# Erolf.net
KiCad netlist of a schematic drawn in EAGLE
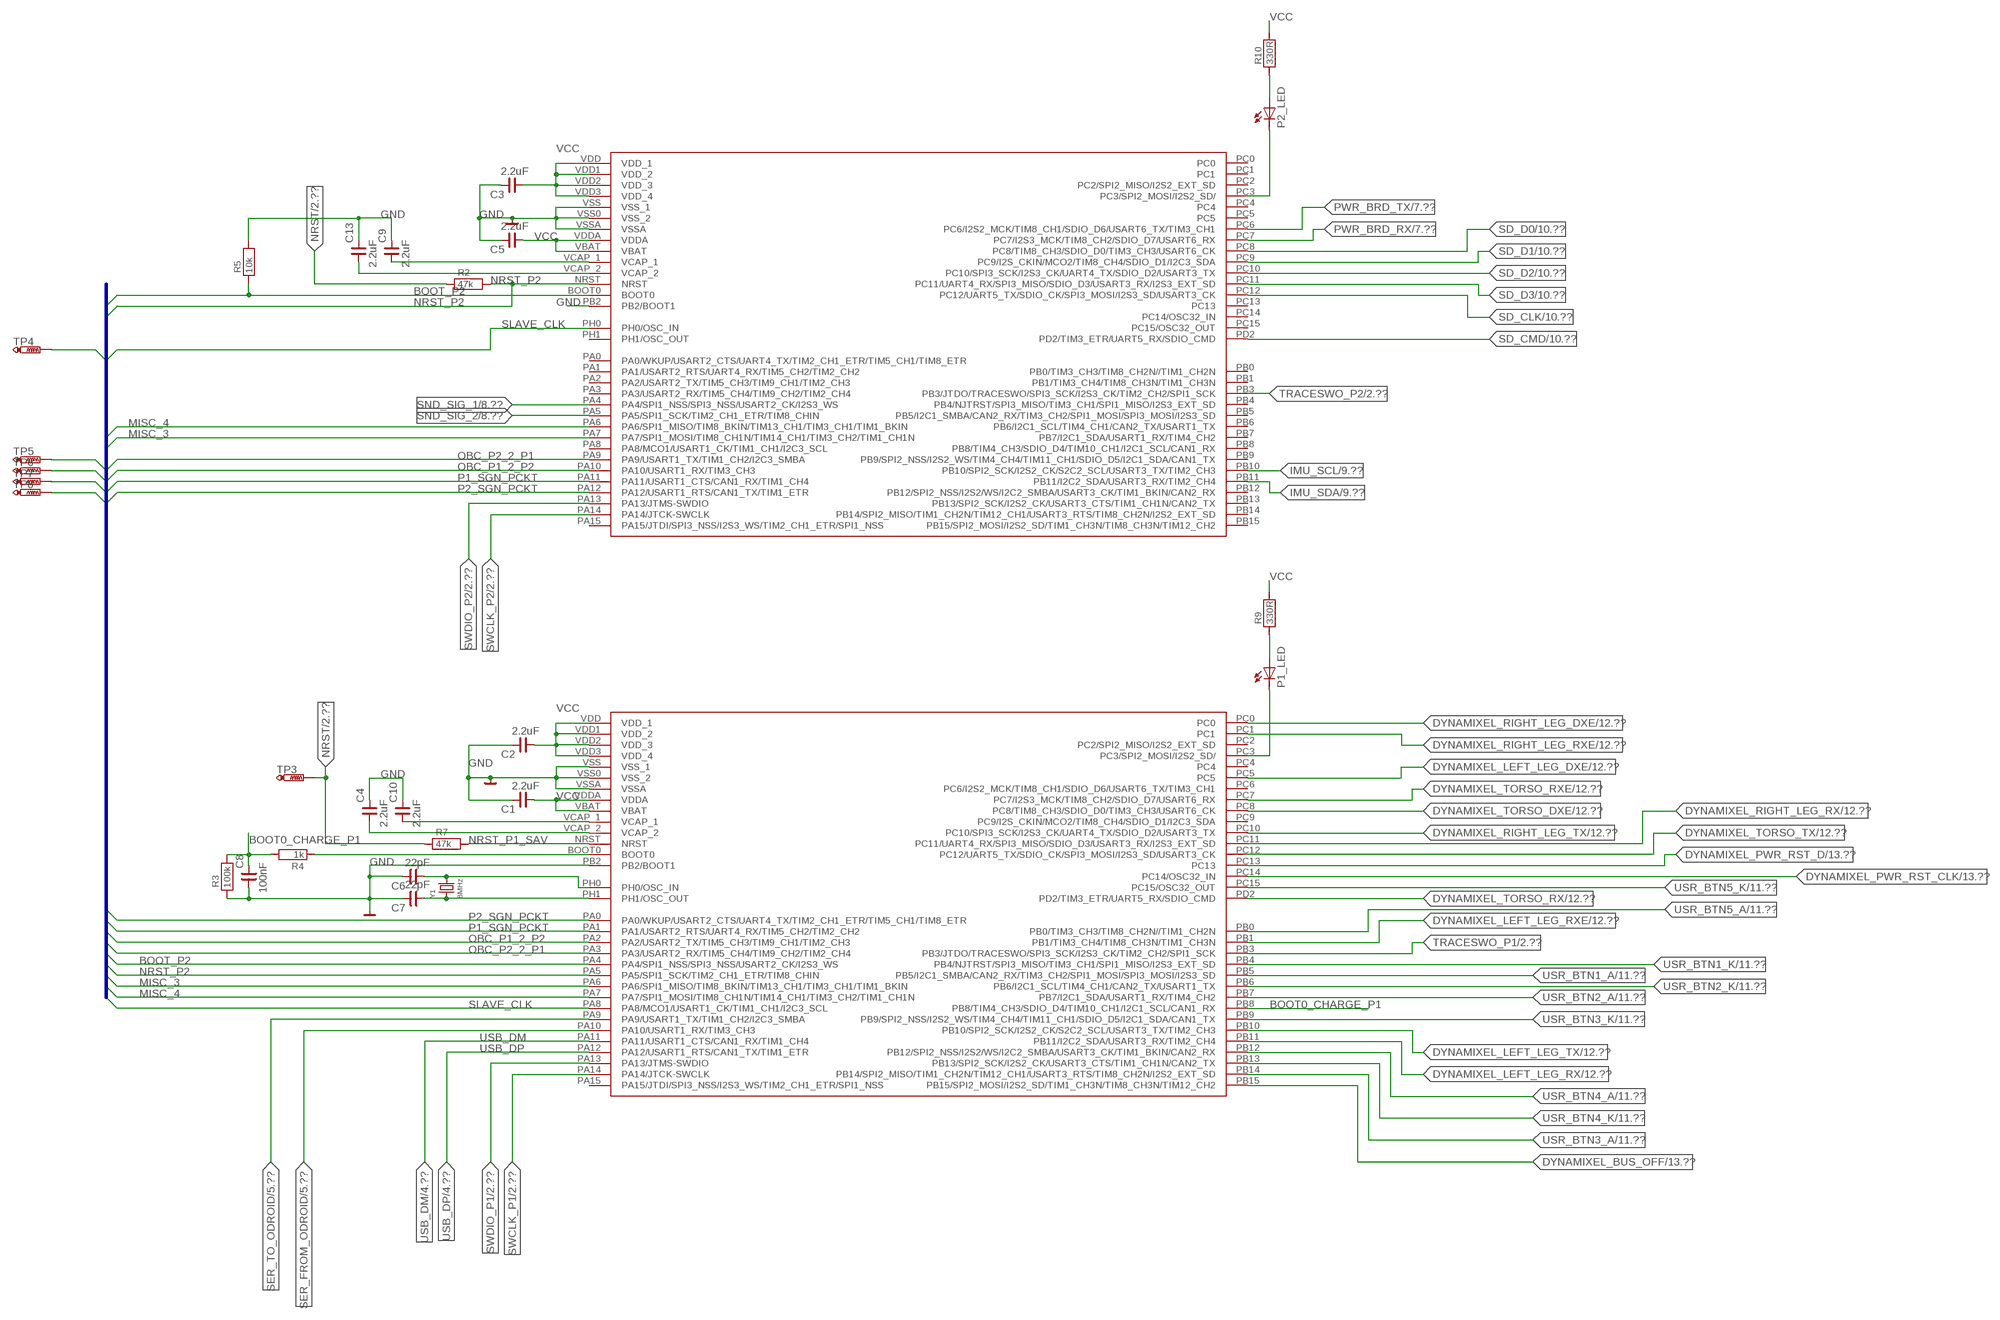
[diagram p0: schematic, sheet 1]
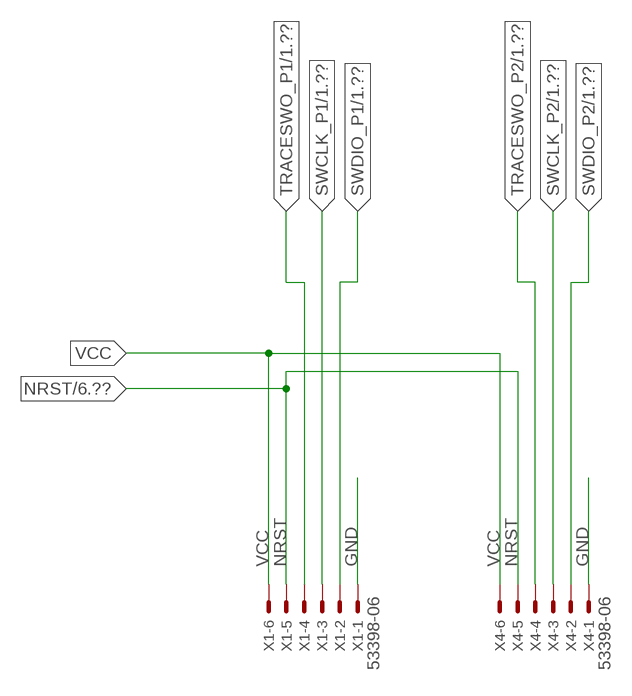
[diagram p1: schematic, sheet 2]
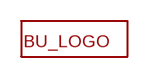
[diagram p2: schematic, sheet 3]
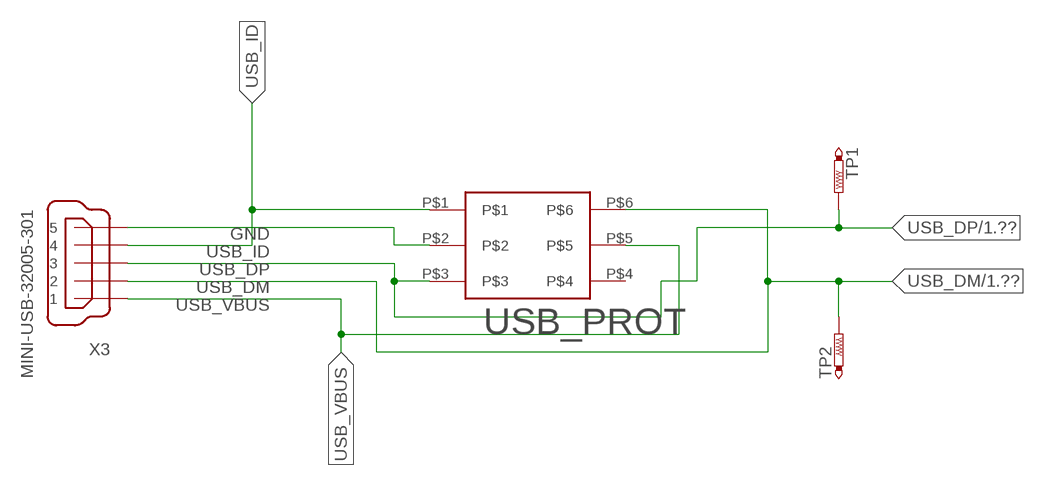
[diagram p3: schematic, sheet 4]
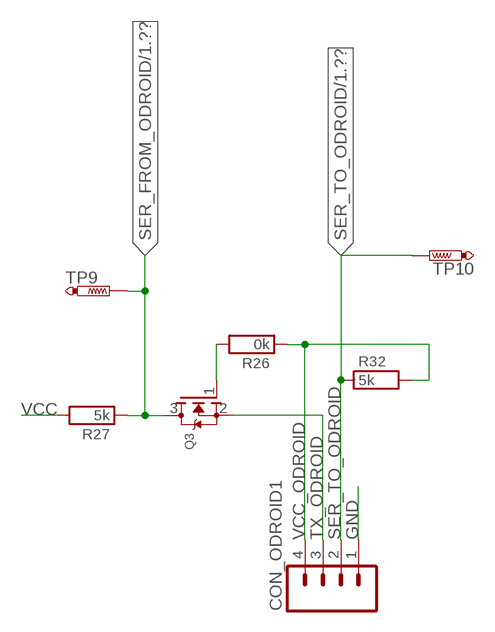
[diagram p4: schematic, sheet 5]
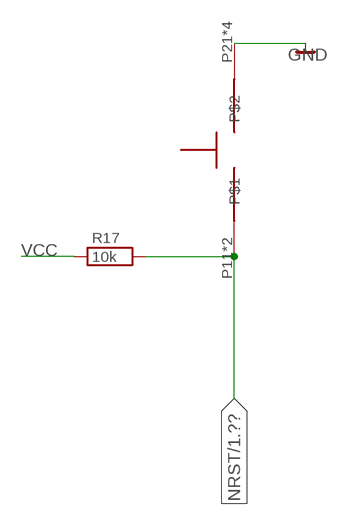
[diagram p5: schematic, sheet 6]
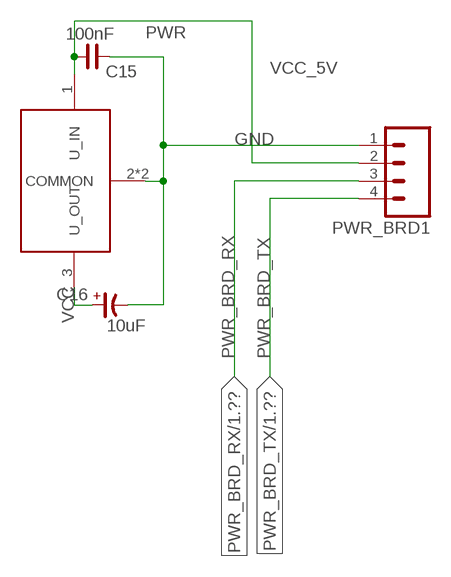
[diagram p6: schematic, sheet 7]
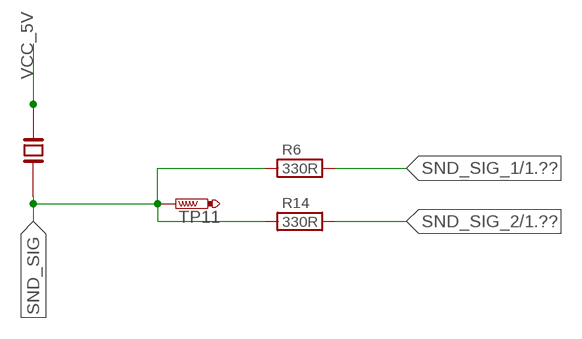
[diagram p7: schematic, sheet 8]
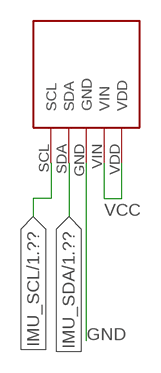
[diagram p8: schematic, sheet 9]
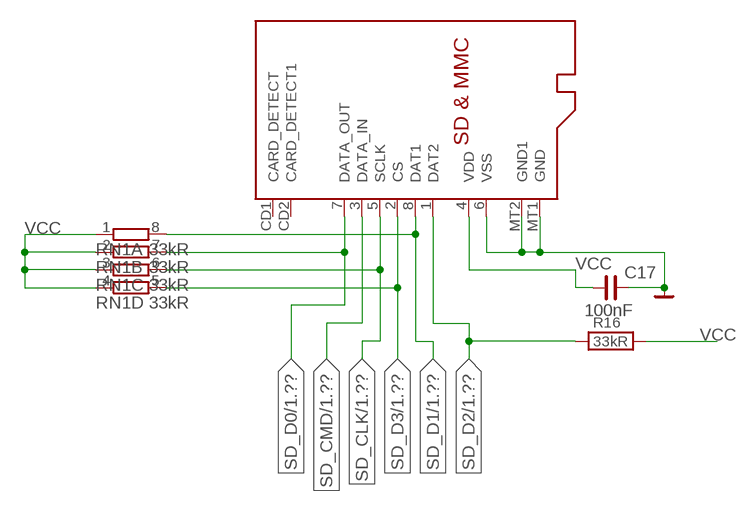
[diagram p9: schematic, sheet 10]
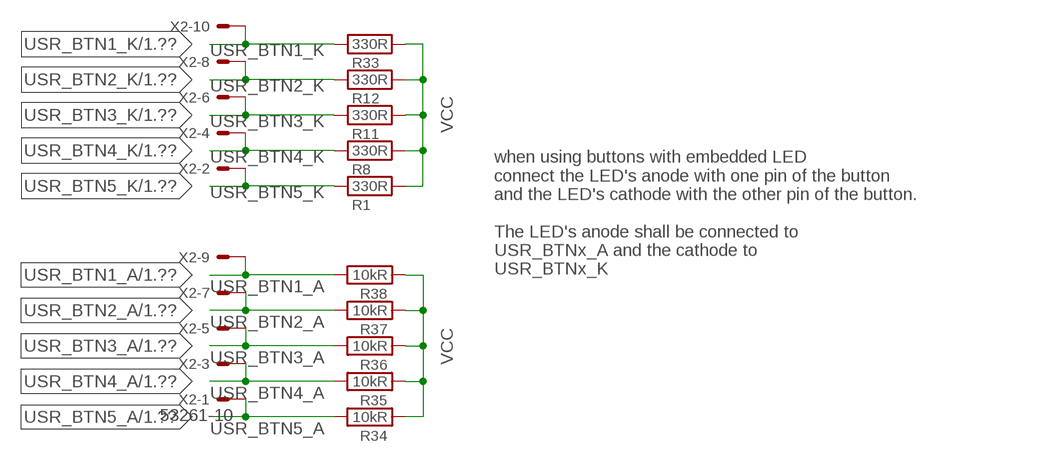
[diagram p10: schematic, sheet 11]
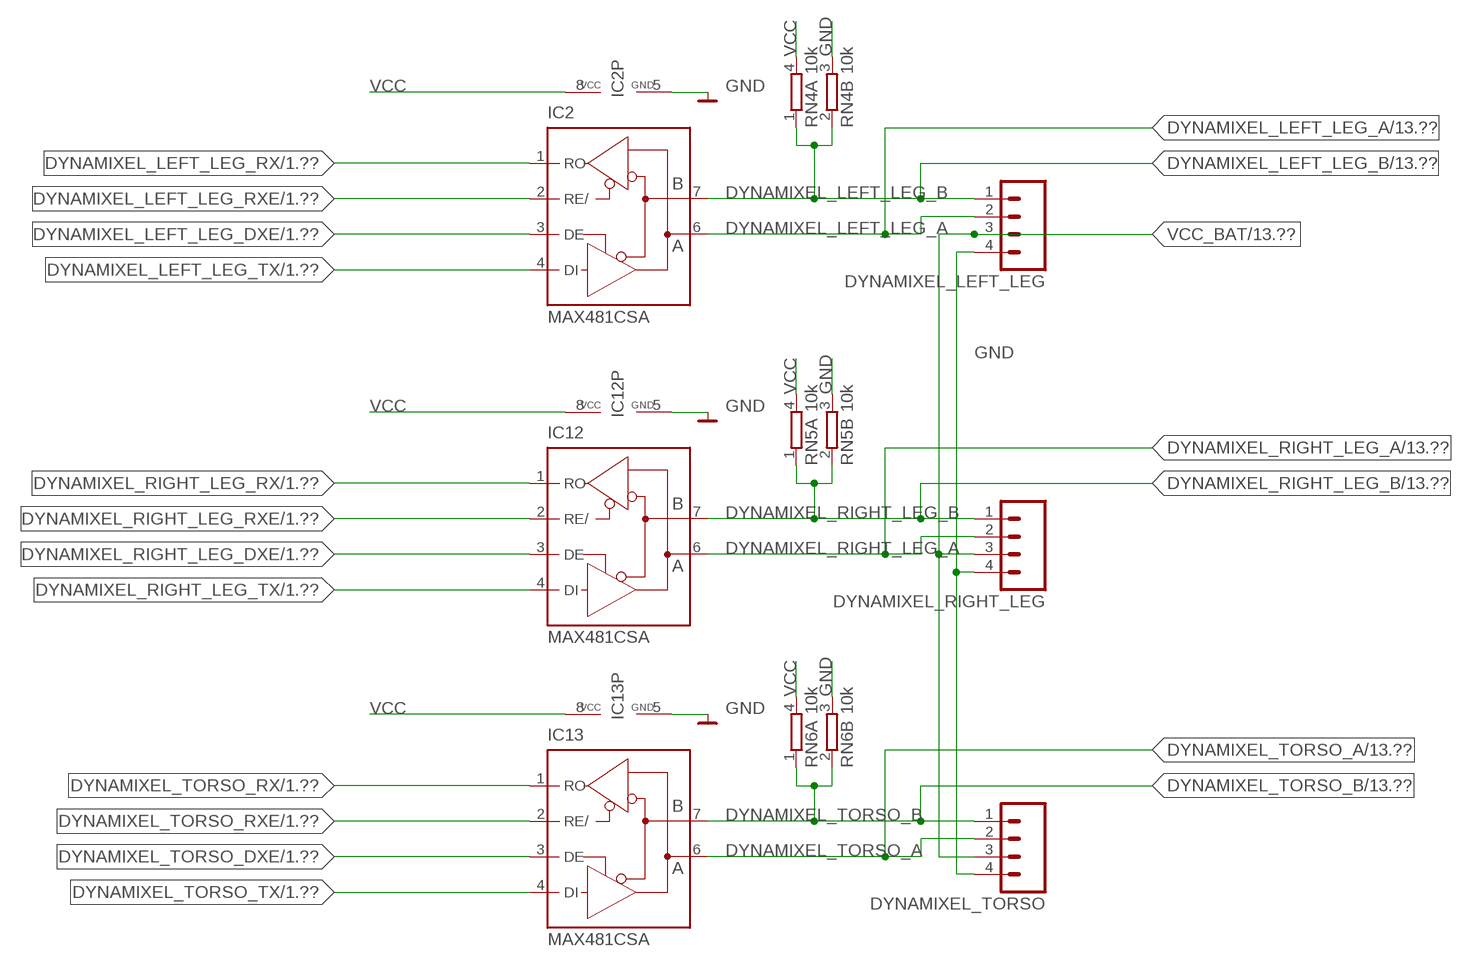
[diagram p11: schematic, sheet 12]
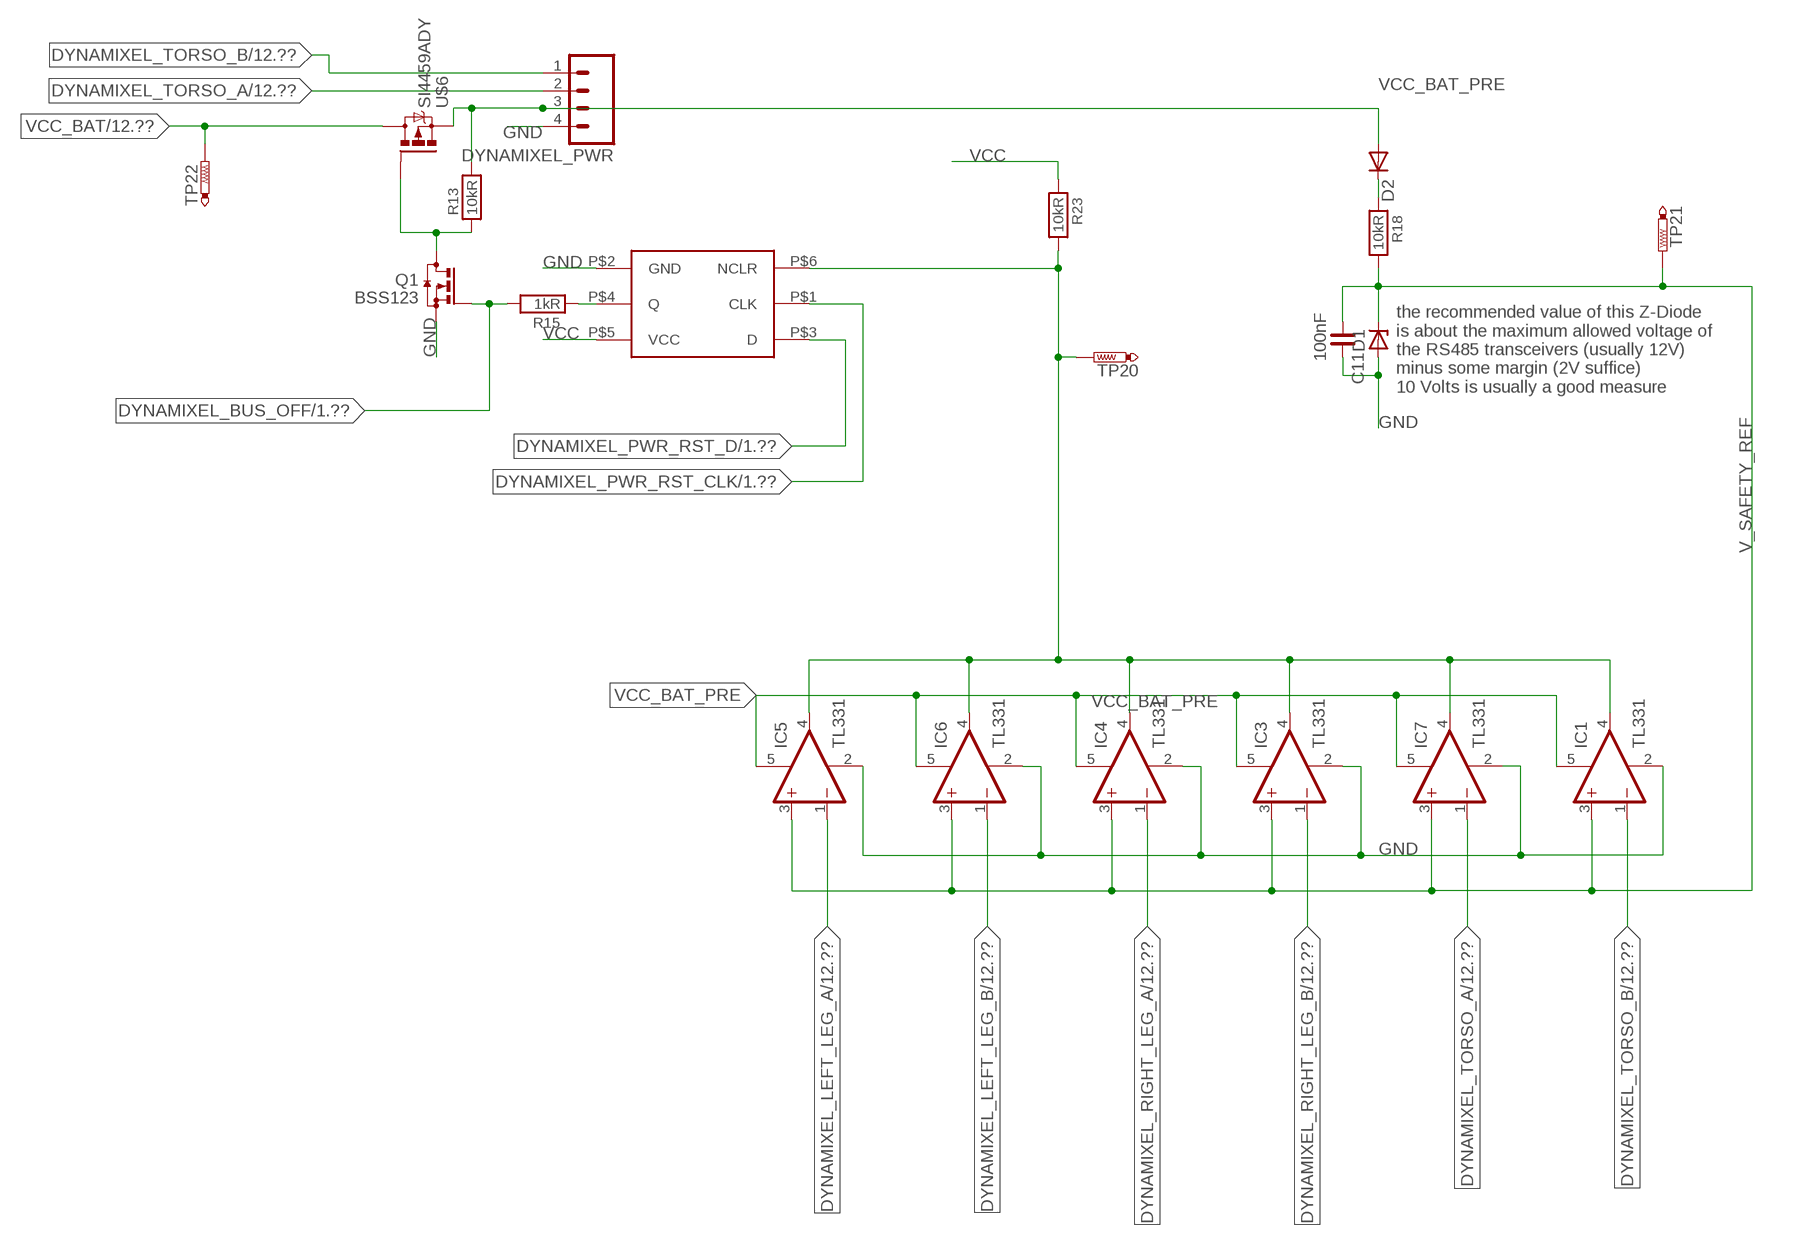
[diagram p12: schematic, sheet 13]

(export (version "E")
  (design (tool "Eeschema 10.0.6"))
  (components
    (comp (ref "TP1")
      (value "PTR1TP06R")
      (footprint "eagle-import:TP06R")
      (libsource (lib "eagle-import") (part "PTR1TP06R"))
    )
    (comp (ref "TP2")
      (value "PTR1TP06R")
      (footprint "eagle-import:TP06R")
      (libsource (lib "eagle-import") (part "PTR1TP06R"))
    )
    (comp (ref "USB_PROT")
      (value "VBUS054B")
      (footprint "eagle-import:LLP75-6L")
      (libsource (lib "eagle-import") (part "VBUS054B"))
    )
    (comp (ref "X3")
      (value "MINI-USB-32005-301")
      (footprint "eagle-import:32005-301")
      (libsource (lib "eagle-import") (part "MINI-USB-32005-301"))
    )
    (comp (ref "R6")
      (value "330R")
      (footprint "eagle-import:R0603")
      (libsource (lib "eagle-import") (part "R0603"))
    )
    (comp (ref "R14")
      (value "330R")
      (footprint "eagle-import:R0603")
      (libsource (lib "eagle-import") (part "R0603"))
    )
    (comp (ref "TP11")
      (value "PTR1TP06R")
      (footprint "eagle-import:TP06R")
      (libsource (lib "eagle-import") (part "PTR1TP06R"))
    )
    (comp (ref "U$1")
      (value "PS1240P02CT3")
      (footprint "eagle-import:PS1240P02CT3")
      (libsource (lib "eagle-import") (part "PS1240P02CT3"))
    )
    (comp (ref "X1")
      (value "53398-06")
      (footprint "eagle-import:53398-06")
      (libsource (lib "eagle-import") (part "53?-06398"))
    )
    (comp (ref "X4")
      (value "53398-06")
      (footprint "eagle-import:53398-06")
      (libsource (lib "eagle-import") (part "53?-06398"))
    )
    (comp (ref "R17")
      (value "10k")
      (footprint "eagle-import:R0603")
      (libsource (lib "eagle-import") (part "R0603"))
    )
    (comp (ref "U$3")
      (value "BUTTON")
      (footprint "eagle-import:BUTTON")
      (libsource (lib "eagle-import") (part "BUTTON"))
    )
    (comp (ref "C1")
      (value "2.2uF")
      (footprint "eagle-import:C0603")
      (libsource (lib "eagle-import") (part "C_0603"))
    )
    (comp (ref "C2")
      (value "2.2uF")
      (footprint "eagle-import:C0603")
      (libsource (lib "eagle-import") (part "C_0603"))
    )
    (comp (ref "C3")
      (value "2.2uF")
      (footprint "eagle-import:C0603")
      (libsource (lib "eagle-import") (part "C_0603"))
    )
    (comp (ref "C4")
      (value "2.2uF")
      (footprint "eagle-import:C0603")
      (libsource (lib "eagle-import") (part "C_0603"))
    )
    (comp (ref "C5")
      (value "2.2uF")
      (footprint "eagle-import:C0603")
      (libsource (lib "eagle-import") (part "C_0603"))
    )
    (comp (ref "C6")
      (value "22pF")
      (footprint "eagle-import:C0603")
      (libsource (lib "eagle-import") (part "C_0603"))
    )
    (comp (ref "C7")
      (value "22pF")
      (footprint "eagle-import:C0603")
      (libsource (lib "eagle-import") (part "C_0603"))
    )
    (comp (ref "C8")
      (value "100nF")
      (footprint "eagle-import:C0603")
      (libsource (lib "eagle-import") (part "C_0603"))
    )
    (comp (ref "C9")
      (value "2.2uF")
      (footprint "eagle-import:C0603")
      (libsource (lib "eagle-import") (part "C_0603"))
    )
    (comp (ref "C10")
      (value "2.2uF")
      (footprint "eagle-import:C0603")
      (libsource (lib "eagle-import") (part "C_0603"))
    )
    (comp (ref "C13")
      (value "2.2uF")
      (footprint "eagle-import:C0603")
      (libsource (lib "eagle-import") (part "C_0603"))
    )
    (comp (ref "P1_LED")
      (value "LEDCHIP-LED0805")
      (footprint "eagle-import:CHIP-LED0805")
      (libsource (lib "eagle-import") (part "LEDCHIP-LED0805"))
    )
    (comp (ref "P2_LED")
      (value "LEDCHIP-LED0805")
      (footprint "eagle-import:CHIP-LED0805")
      (libsource (lib "eagle-import") (part "LEDCHIP-LED0805"))
    )
    (comp (ref "PROCESSOR_1")
      (value "STM32-F405RB")
      (footprint "eagle-import:LQFP-64")
      (libsource (lib "eagle-import") (part "STM32-F405RB"))
    )
    (comp (ref "PROCESSOR_2")
      (value "STM32-F405RB")
      (footprint "eagle-import:LQFP-64")
      (libsource (lib "eagle-import") (part "STM32-F405RB"))
    )
    (comp (ref "R2")
      (value "47k")
      (footprint "eagle-import:R0603")
      (libsource (lib "eagle-import") (part "R0603"))
    )
    (comp (ref "R3")
      (value "100k")
      (footprint "eagle-import:R0603")
      (libsource (lib "eagle-import") (part "R0603"))
    )
    (comp (ref "R4")
      (value "1k")
      (footprint "eagle-import:R0603")
      (libsource (lib "eagle-import") (part "R0603"))
    )
    (comp (ref "R5")
      (value "10k")
      (footprint "eagle-import:R0603")
      (libsource (lib "eagle-import") (part "R0603"))
    )
    (comp (ref "R7")
      (value "47k")
      (footprint "eagle-import:R0603")
      (libsource (lib "eagle-import") (part "R0603"))
    )
    (comp (ref "R9")
      (value "330R")
      (footprint "eagle-import:R0603")
      (libsource (lib "eagle-import") (part "R0603"))
    )
    (comp (ref "R10")
      (value "330R")
      (footprint "eagle-import:R0603")
      (libsource (lib "eagle-import") (part "R0603"))
    )
    (comp (ref "TP3")
      (value "PTR1TP06R")
      (footprint "eagle-import:TP06R")
      (libsource (lib "eagle-import") (part "PTR1TP06R"))
    )
    (comp (ref "TP4")
      (value "PTR1TP06R")
      (footprint "eagle-import:TP06R")
      (libsource (lib "eagle-import") (part "PTR1TP06R"))
    )
    (comp (ref "TP5")
      (value "PTR1TP06R")
      (footprint "eagle-import:TP06R")
      (libsource (lib "eagle-import") (part "PTR1TP06R"))
    )
    (comp (ref "TP6")
      (value "PTR1TP06R")
      (footprint "eagle-import:TP06R")
      (libsource (lib "eagle-import") (part "PTR1TP06R"))
    )
    (comp (ref "TP7")
      (value "PTR1TP06R")
      (footprint "eagle-import:TP06R")
      (libsource (lib "eagle-import") (part "PTR1TP06R"))
    )
    (comp (ref "TP8")
      (value "PTR1TP06R")
      (footprint "eagle-import:TP06R")
      (libsource (lib "eagle-import") (part "PTR1TP06R"))
    )
    (comp (ref "Y1")
      (value "8MHz")
      (footprint "eagle-import:CRYSTAL_4.9X1.8")
      (libsource (lib "eagle-import") (part "CRYSTALTHIN32K"))
    )
    (comp (ref "C11")
      (value "100nF")
      (footprint "eagle-import:C0603")
      (libsource (lib "eagle-import") (part "C_0603"))
    )
    (comp (ref "D1")
      (value "ZENER-DIODESOD80C")
      (footprint "eagle-import:SOD80C")
      (libsource (lib "eagle-import") (part "ZENER-DIODESOD80C"))
    )
    (comp (ref "D2")
      (value "DIODE-MICROMELF-R")
      (footprint "eagle-import:MICROMELF-R")
      (libsource (lib "eagle-import") (part "DIODE-MICROMELF-R"))
    )
    (comp (ref "DYNAMIXEL_PWR")
      (value "M04")
      (footprint "eagle-import:04P")
      (libsource (lib "eagle-import") (part "M04"))
    )
    (comp (ref "IC1")
      (value "TL331")
      (footprint "eagle-import:DBV-R-PDSO-G5")
      (libsource (lib "eagle-import") (part "TL331"))
    )
    (comp (ref "IC3")
      (value "TL331")
      (footprint "eagle-import:DBV-R-PDSO-G5")
      (libsource (lib "eagle-import") (part "TL331"))
    )
    (comp (ref "IC4")
      (value "TL331")
      (footprint "eagle-import:DBV-R-PDSO-G5")
      (libsource (lib "eagle-import") (part "TL331"))
    )
    (comp (ref "IC5")
      (value "TL331")
      (footprint "eagle-import:DBV-R-PDSO-G5")
      (libsource (lib "eagle-import") (part "TL331"))
    )
    (comp (ref "IC6")
      (value "TL331")
      (footprint "eagle-import:DBV-R-PDSO-G5")
      (libsource (lib "eagle-import") (part "TL331"))
    )
    (comp (ref "IC7")
      (value "TL331")
      (footprint "eagle-import:DBV-R-PDSO-G5")
      (libsource (lib "eagle-import") (part "TL331"))
    )
    (comp (ref "Q1")
      (value "BSS123")
      (footprint "eagle-import:SOT23")
      (libsource (lib "eagle-import") (part "BSS123"))
    )
    (comp (ref "R13")
      (value "10kR")
      (footprint "eagle-import:R0603")
      (libsource (lib "eagle-import") (part "R0603"))
    )
    (comp (ref "R15")
      (value "1kR")
      (footprint "eagle-import:R0603")
      (libsource (lib "eagle-import") (part "R0603"))
    )
    (comp (ref "R18")
      (value "10kR")
      (footprint "eagle-import:R0603")
      (libsource (lib "eagle-import") (part "R0603"))
    )
    (comp (ref "R23")
      (value "10kR")
      (footprint "eagle-import:R0603")
      (libsource (lib "eagle-import") (part "R0603"))
    )
    (comp (ref "TP20")
      (value "PTR1TP06R")
      (footprint "eagle-import:TP06R")
      (libsource (lib "eagle-import") (part "PTR1TP06R"))
    )
    (comp (ref "TP21")
      (value "PTR1TP06R")
      (footprint "eagle-import:TP06R")
      (libsource (lib "eagle-import") (part "PTR1TP06R"))
    )
    (comp (ref "TP22")
      (value "PTR1TP06R")
      (footprint "eagle-import:TP06R")
      (libsource (lib "eagle-import") (part "PTR1TP06R"))
    )
    (comp (ref "U$6")
      (value "SI4459ADY")
      (footprint "eagle-import:SO-8")
      (libsource (lib "eagle-import") (part "SI4459ADY"))
    )
    (comp (ref "U$7")
      (value "SN74LVC1G175")
      (footprint "eagle-import:DCV_R-PDSO-6")
      (libsource (lib "eagle-import") (part "SN74LVC1G175"))
    )
    (comp (ref "CON_ODROID1")
      (value "M04")
      (footprint "eagle-import:04P")
      (fields (field (name "OC_FARNELL") "unknown") (field (name "OC_NEWARK") "unknown"))
      (libsource (lib "eagle-import") (part "M04"))
    )
    (comp (ref "Q3")
      (value "MOSFET-NREFLOW")
      (footprint "eagle-import:SOT23")
      (libsource (lib "eagle-import") (part "MOSFET-NREFLOW"))
    )
    (comp (ref "R26")
      (value "0k")
      (footprint "eagle-import:R0603")
      (libsource (lib "eagle-import") (part "R0603"))
    )
    (comp (ref "R27")
      (value "5k")
      (footprint "eagle-import:R0603")
      (libsource (lib "eagle-import") (part "R0603"))
    )
    (comp (ref "R32")
      (value "5k")
      (footprint "eagle-import:R0603")
      (libsource (lib "eagle-import") (part "R0603"))
    )
    (comp (ref "TP9")
      (value "PTR1TP06R")
      (footprint "eagle-import:TP06R")
      (libsource (lib "eagle-import") (part "PTR1TP06R"))
    )
    (comp (ref "TP10")
      (value "PTR1TP06R")
      (footprint "eagle-import:TP06R")
      (libsource (lib "eagle-import") (part "PTR1TP06R"))
    )
    (comp (ref "DYNAMIXEL_LEFT_LEG")
      (value "M04")
      (footprint "eagle-import:04P")
      (libsource (lib "eagle-import") (part "M04"))
    )
    (comp (ref "DYNAMIXEL_RIGHT_LEG")
      (value "M04")
      (footprint "eagle-import:04P")
      (libsource (lib "eagle-import") (part "M04"))
    )
    (comp (ref "DYNAMIXEL_TORSO")
      (value "M04")
      (footprint "eagle-import:04P")
      (libsource (lib "eagle-import") (part "M04"))
    )
    (comp (ref "IC2")
      (value "MAX481CSA")
      (footprint "eagle-import:SO08")
      (fields (field (name "MF") "MAXIM"))
      (libsource (lib "eagle-import") (part "MAX481CSA"))
    )
    (comp (ref "IC12")
      (value "MAX481CSA")
      (footprint "eagle-import:SO08")
      (fields (field (name "MF") "MAXIM"))
      (libsource (lib "eagle-import") (part "MAX481CSA"))
    )
    (comp (ref "IC13")
      (value "MAX481CSA")
      (footprint "eagle-import:SO08")
      (fields (field (name "MF") "MAXIM"))
      (libsource (lib "eagle-import") (part "MAX481CSA"))
    )
    (comp (ref "RN4")
      (value "10k")
      (footprint "eagle-import:EXBV4V")
      (libsource (lib "eagle-import") (part "2R-NEXBV4V"))
    )
    (comp (ref "RN5")
      (value "10k")
      (footprint "eagle-import:EXBV4V")
      (libsource (lib "eagle-import") (part "2R-NEXBV4V"))
    )
    (comp (ref "RN6")
      (value "10k")
      (footprint "eagle-import:EXBV4V")
      (libsource (lib "eagle-import") (part "2R-NEXBV4V"))
    )
    (comp (ref "R1")
      (value "330R")
      (footprint "eagle-import:R0603")
      (libsource (lib "eagle-import") (part "R0603"))
    )
    (comp (ref "R8")
      (value "330R")
      (footprint "eagle-import:R0603")
      (libsource (lib "eagle-import") (part "R0603"))
    )
    (comp (ref "R11")
      (value "330R")
      (footprint "eagle-import:R0603")
      (libsource (lib "eagle-import") (part "R0603"))
    )
    (comp (ref "R12")
      (value "330R")
      (footprint "eagle-import:R0603")
      (libsource (lib "eagle-import") (part "R0603"))
    )
    (comp (ref "R33")
      (value "330R")
      (footprint "eagle-import:R0603")
      (libsource (lib "eagle-import") (part "R0603"))
    )
    (comp (ref "R34")
      (value "10kR")
      (footprint "eagle-import:R0603")
      (libsource (lib "eagle-import") (part "R0603"))
    )
    (comp (ref "R35")
      (value "10kR")
      (footprint "eagle-import:R0603")
      (libsource (lib "eagle-import") (part "R0603"))
    )
    (comp (ref "R36")
      (value "10kR")
      (footprint "eagle-import:R0603")
      (libsource (lib "eagle-import") (part "R0603"))
    )
    (comp (ref "R37")
      (value "10kR")
      (footprint "eagle-import:R0603")
      (libsource (lib "eagle-import") (part "R0603"))
    )
    (comp (ref "R38")
      (value "10kR")
      (footprint "eagle-import:R0603")
      (libsource (lib "eagle-import") (part "R0603"))
    )
    (comp (ref "X2")
      (value "53261-10")
      (footprint "eagle-import:53261-10")
      (libsource (lib "eagle-import") (part "53?-10261"))
    )
    (comp (ref "U$8")
      (value "LOGO")
      (footprint "eagle-import:LOGO")
      (libsource (lib "eagle-import") (part "LOGO"))
    )
    (comp (ref "U$4")
      (value "MINI-IMU-9V2")
      (footprint "eagle-import:PCB")
      (libsource (lib "eagle-import") (part "MINI-IMU-9V2"))
    )
    (comp (ref "BLUBB")
      (value "UA78M00")
      (footprint "eagle-import:SOT223-4")
      (libsource (lib "eagle-import") (part "UA78M00"))
    )
    (comp (ref "C15")
      (value "100nF")
      (footprint "eagle-import:C0603")
      (libsource (lib "eagle-import") (part "C_0603"))
    )
    (comp (ref "C16")
      (value "10uF")
      (footprint "eagle-import:CE-025X060")
      (libsource (lib "eagle-import") (part "CP_E-025X060"))
    )
    (comp (ref "PWR_BRD1")
      (value "M04")
      (footprint "eagle-import:04P")
      (fields (field (name "OC_FARNELL") "unknown") (field (name "OC_NEWARK") "unknown"))
      (libsource (lib "eagle-import") (part "M04"))
    )
    (comp (ref "C17")
      (value "100nF")
      (footprint "eagle-import:C0603")
      (libsource (lib "eagle-import") (part "C_0603"))
    )
    (comp (ref "R16")
      (value "33kR")
      (footprint "eagle-import:R0603")
      (libsource (lib "eagle-import") (part "R0603"))
    )
    (comp (ref "RN1")
      (value "33kR")
      (footprint "eagle-import:EXBS8V")
      (libsource (lib "eagle-import") (part "4R-NEXBS8V"))
    )
    (comp (ref "U$2")
      (value "MICROSD")
      (footprint "eagle-import:MICROSD")
      (libsource (lib "eagle-import") (part "MICROSD"))
    )
  )
  (nets
    (net (code "1") (name "BOOT0_CHARGE_P1") (class "Default")
      (node (ref "C8") (pin "2") (pinfunction "2_2") (pintype "passive"))
      (node (ref "PROCESSOR_1") (pin "PB8") (pinfunction "PB8/TIM4_CH3/SDIO_D4/TIM10_CH1/I2C1_SCL/CAN1_RX_PB8") (pintype "bidirectional"))
      (node (ref "R3") (pin "2") (pinfunction "2_2") (pintype "passive"))
      (node (ref "R4") (pin "2") (pinfunction "2_2") (pintype "passive"))
    )
    (net (code "2") (name "BOOT_P2") (class "Default")
      (node (ref "PROCESSOR_1") (pin "PA4") (pinfunction "PA4/SPI1_NSS/SPI3_NSS/USART2_CK/I2S3_WS_PA4") (pintype "bidirectional"))
      (node (ref "PROCESSOR_2") (pin "BOOT0") (pinfunction "BOOT0_BOOT0") (pintype "bidirectional"))
      (node (ref "R5") (pin "1") (pinfunction "1_1") (pintype "passive"))
    )
    (net (code "3") (name "DYNAMIXEL_BUS_OFF") (class "Default")
      (node (ref "PROCESSOR_1") (pin "PB15") (pinfunction "PB15/SPI2_MOSI/I2S2_SD/TIM1_CH3N/TIM8_CH3N/TIM12_CH2_PB15") (pintype "bidirectional"))
      (node (ref "Q1") (pin "1") (pinfunction "G_1") (pintype "passive"))
      (node (ref "R15") (pin "2") (pinfunction "2_2") (pintype "passive"))
    )
    (net (code "4") (name "DYNAMIXEL_LEFT_LEG_A") (class "Default")
      (node (ref "DYNAMIXEL_LEFT_LEG") (pin "2") (pinfunction "2_2") (pintype "passive"))
      (node (ref "IC2") (pin "6") (pinfunction "A_6") (pintype "passive"))
      (node (ref "IC5") (pin "1") (pinfunction "-IN_1") (pintype "input"))
    )
    (net (code "5") (name "DYNAMIXEL_LEFT_LEG_B") (class "Default")
      (node (ref "DYNAMIXEL_LEFT_LEG") (pin "1") (pinfunction "1_1") (pintype "passive"))
      (node (ref "IC2") (pin "7") (pinfunction "B_7") (pintype "passive"))
      (node (ref "IC6") (pin "1") (pinfunction "-IN_1") (pintype "input"))
      (node (ref "RN4") (pin "1") (pinfunction "1_1") (pintype "passive"))
      (node (ref "RN4") (pin "2") (pinfunction "1_2") (pintype "passive"))
    )
    (net (code "6") (name "DYNAMIXEL_LEFT_LEG_DXE") (class "Default")
      (node (ref "IC2") (pin "3") (pinfunction "DE_3") (pintype "input"))
      (node (ref "PROCESSOR_1") (pin "PC5") (pinfunction "PC5_PC5") (pintype "bidirectional"))
    )
    (net (code "7") (name "DYNAMIXEL_LEFT_LEG_RX") (class "Default")
      (node (ref "IC2") (pin "1") (pinfunction "RO_1") (pintype "output"))
      (node (ref "PROCESSOR_1") (pin "PB11") (pinfunction "PB11/I2C2_SDA/USART3_RX/TIM2_CH4_PB11") (pintype "bidirectional"))
    )
    (net (code "8") (name "DYNAMIXEL_LEFT_LEG_RXE") (class "Default")
      (node (ref "IC2") (pin "2") (pinfunction "RE/_2") (pintype "input"))
      (node (ref "PROCESSOR_1") (pin "PB1") (pinfunction "PB1/TIM3_CH4/TIM8_CH3N/TIM1_CH3N_PB1") (pintype "bidirectional"))
    )
    (net (code "9") (name "DYNAMIXEL_LEFT_LEG_TX") (class "Default")
      (node (ref "IC2") (pin "4") (pinfunction "DI_4") (pintype "input"))
      (node (ref "PROCESSOR_1") (pin "PB10") (pinfunction "PB10/SPI2_SCK/I2S2_CK/S2C2_SCL/USART3_TX/TIM2_CH3_PB10") (pintype "bidirectional"))
    )
    (net (code "10") (name "DYNAMIXEL_PWR_RST_CLK") (class "Default")
      (node (ref "PROCESSOR_1") (pin "PC14") (pinfunction "PC14/OSC32_IN_PC14") (pintype "bidirectional"))
      (node (ref "U$7") (pin "P$1") (pinfunction "CLK_P$1") (pintype "bidirectional"))
    )
    (net (code "11") (name "DYNAMIXEL_PWR_RST_D") (class "Default")
      (node (ref "PROCESSOR_1") (pin "PC13") (pinfunction "PC13_PC13") (pintype "bidirectional"))
      (node (ref "U$7") (pin "P$3") (pinfunction "D_P$3") (pintype "bidirectional"))
    )
    (net (code "12") (name "DYNAMIXEL_RIGHT_LEG_A") (class "Default")
      (node (ref "DYNAMIXEL_RIGHT_LEG") (pin "2") (pinfunction "2_2") (pintype "passive"))
      (node (ref "IC12") (pin "6") (pinfunction "A_6") (pintype "passive"))
      (node (ref "IC4") (pin "1") (pinfunction "-IN_1") (pintype "input"))
    )
    (net (code "13") (name "DYNAMIXEL_RIGHT_LEG_B") (class "Default")
      (node (ref "DYNAMIXEL_RIGHT_LEG") (pin "1") (pinfunction "1_1") (pintype "passive"))
      (node (ref "IC12") (pin "7") (pinfunction "B_7") (pintype "passive"))
      (node (ref "IC3") (pin "1") (pinfunction "-IN_1") (pintype "input"))
      (node (ref "RN5") (pin "1") (pinfunction "1_1") (pintype "passive"))
      (node (ref "RN5") (pin "2") (pinfunction "1_2") (pintype "passive"))
    )
    (net (code "14") (name "DYNAMIXEL_RIGHT_LEG_DXE") (class "Default")
      (node (ref "IC12") (pin "3") (pinfunction "DE_3") (pintype "input"))
      (node (ref "PROCESSOR_1") (pin "PC0") (pinfunction "PC0_PC0") (pintype "bidirectional"))
    )
    (net (code "15") (name "DYNAMIXEL_RIGHT_LEG_RX") (class "Default")
      (node (ref "IC12") (pin "1") (pinfunction "RO_1") (pintype "output"))
      (node (ref "PROCESSOR_1") (pin "PC11") (pinfunction "PC11/UART4_RX/SPI3_MISO/SDIO_D3/USART3_RX/I2S3_EXT_SD_PC11") (pintype "bidirectional"))
    )
    (net (code "16") (name "DYNAMIXEL_RIGHT_LEG_RXE") (class "Default")
      (node (ref "IC12") (pin "2") (pinfunction "RE/_2") (pintype "input"))
      (node (ref "PROCESSOR_1") (pin "PC1") (pinfunction "PC1_PC1") (pintype "bidirectional"))
    )
    (net (code "17") (name "DYNAMIXEL_RIGHT_LEG_TX") (class "Default")
      (node (ref "IC12") (pin "4") (pinfunction "DI_4") (pintype "input"))
      (node (ref "PROCESSOR_1") (pin "PC10") (pinfunction "PC10/SPI3_SCK/I2S3_CK/UART4_TX/SDIO_D2/USART3_TX_PC10") (pintype "bidirectional"))
    )
    (net (code "18") (name "DYNAMIXEL_TORSO_A") (class "Default")
      (node (ref "DYNAMIXEL_PWR") (pin "2") (pinfunction "2_2") (pintype "passive"))
      (node (ref "DYNAMIXEL_TORSO") (pin "2") (pinfunction "2_2") (pintype "passive"))
      (node (ref "IC13") (pin "6") (pinfunction "A_6") (pintype "passive"))
      (node (ref "IC7") (pin "1") (pinfunction "-IN_1") (pintype "input"))
    )
    (net (code "19") (name "DYNAMIXEL_TORSO_B") (class "Default")
      (node (ref "DYNAMIXEL_PWR") (pin "1") (pinfunction "1_1") (pintype "passive"))
      (node (ref "DYNAMIXEL_TORSO") (pin "1") (pinfunction "1_1") (pintype "passive"))
      (node (ref "IC1") (pin "1") (pinfunction "-IN_1") (pintype "input"))
      (node (ref "IC13") (pin "7") (pinfunction "B_7") (pintype "passive"))
      (node (ref "RN6") (pin "1") (pinfunction "1_1") (pintype "passive"))
      (node (ref "RN6") (pin "2") (pinfunction "1_2") (pintype "passive"))
    )
    (net (code "20") (name "DYNAMIXEL_TORSO_DXE") (class "Default")
      (node (ref "IC13") (pin "3") (pinfunction "DE_3") (pintype "input"))
      (node (ref "PROCESSOR_1") (pin "PC8") (pinfunction "PC8/TIM8_CH3/SDIO_D0/TIM3_CH3/USART6_CK_PC8") (pintype "bidirectional"))
    )
    (net (code "21") (name "DYNAMIXEL_TORSO_RX") (class "Default")
      (node (ref "IC13") (pin "1") (pinfunction "RO_1") (pintype "output"))
      (node (ref "PROCESSOR_1") (pin "PD2") (pinfunction "PD2/TIM3_ETR/UART5_RX/SDIO_CMD_PD2") (pintype "bidirectional"))
    )
    (net (code "22") (name "DYNAMIXEL_TORSO_RXE") (class "Default")
      (node (ref "IC13") (pin "2") (pinfunction "RE/_2") (pintype "input"))
      (node (ref "PROCESSOR_1") (pin "PC7") (pinfunction "PC7/I2S3_MCK/TIM8_CH2/SDIO_D7/USART6_RX_PC7") (pintype "bidirectional"))
    )
    (net (code "23") (name "DYNAMIXEL_TORSO_TX") (class "Default")
      (node (ref "IC13") (pin "4") (pinfunction "DI_4") (pintype "input"))
      (node (ref "PROCESSOR_1") (pin "PC12") (pinfunction "PC12/UART5_TX/SDIO_CK/SPI3_MOSI/I2S3_SD/USART3_CK_PC12") (pintype "bidirectional"))
    )
    (net (code "24") (name "GND") (class "Default")
      (node (ref "BLUBB") (pin "2") (pinfunction "COMMON_2") (pintype "bidirectional"))
      (node (ref "BLUBB") (pin "4") (pinfunction "COMMON_4") (pintype "bidirectional"))
      (node (ref "C1") (pin "2") (pinfunction "2_2") (pintype "passive"))
      (node (ref "C10") (pin "2") (pinfunction "2_2") (pintype "passive"))
      (node (ref "C11") (pin "2") (pinfunction "2_2") (pintype "passive"))
      (node (ref "C13") (pin "2") (pinfunction "2_2") (pintype "passive"))
      (node (ref "C15") (pin "2") (pinfunction "2_2") (pintype "passive"))
      (node (ref "C16") (pin "-") (pinfunction "-_-") (pintype "passive"))
      (node (ref "C17") (pin "2") (pinfunction "2_2") (pintype "passive"))
      (node (ref "C2") (pin "2") (pinfunction "2_2") (pintype "passive"))
      (node (ref "C3") (pin "2") (pinfunction "2_2") (pintype "passive"))
      (node (ref "C4") (pin "2") (pinfunction "2_2") (pintype "passive"))
      (node (ref "C5") (pin "2") (pinfunction "2_2") (pintype "passive"))
      (node (ref "C6") (pin "2") (pinfunction "2_2") (pintype "passive"))
      (node (ref "C7") (pin "2") (pinfunction "2_2") (pintype "passive"))
      (node (ref "C8") (pin "1") (pinfunction "1_1") (pintype "passive"))
      (node (ref "C9") (pin "2") (pinfunction "2_2") (pintype "passive"))
      (node (ref "CON_ODROID1") (pin "1") (pinfunction "1_1") (pintype "passive"))
      (node (ref "D1") (pin "A") (pinfunction "A_A") (pintype "passive"))
      (node (ref "DYNAMIXEL_LEFT_LEG") (pin "4") (pinfunction "4_4") (pintype "passive"))
      (node (ref "DYNAMIXEL_PWR") (pin "4") (pinfunction "4_4") (pintype "passive"))
      (node (ref "DYNAMIXEL_RIGHT_LEG") (pin "4") (pinfunction "4_4") (pintype "passive"))
      (node (ref "DYNAMIXEL_TORSO") (pin "4") (pinfunction "4_4") (pintype "passive"))
      (node (ref "IC1") (pin "2") (pinfunction "GND_2") (pintype "power_in"))
      (node (ref "IC12") (pin "5") (pinfunction "GND_5") (pintype "power_in"))
      (node (ref "IC13") (pin "5") (pinfunction "GND_5") (pintype "power_in"))
      (node (ref "IC2") (pin "5") (pinfunction "GND_5") (pintype "power_in"))
      (node (ref "IC3") (pin "2") (pinfunction "GND_2") (pintype "power_in"))
      (node (ref "IC4") (pin "2") (pinfunction "GND_2") (pintype "power_in"))
      (node (ref "IC5") (pin "2") (pinfunction "GND_2") (pintype "power_in"))
      (node (ref "IC6") (pin "2") (pinfunction "GND_2") (pintype "power_in"))
      (node (ref "IC7") (pin "2") (pinfunction "GND_2") (pintype "power_in"))
      (node (ref "PROCESSOR_1") (pin "PB2") (pinfunction "PB2/BOOT1_PB2") (pintype "bidirectional"))
      (node (ref "PROCESSOR_1") (pin "VSS") (pinfunction "VSS_1_VSS") (pintype "bidirectional"))
      (node (ref "PROCESSOR_1") (pin "VSS0") (pinfunction "VSS_2_VSS0") (pintype "bidirectional"))
      (node (ref "PROCESSOR_1") (pin "VSSA") (pinfunction "VSSA_VSSA") (pintype "bidirectional"))
      (node (ref "PROCESSOR_2") (pin "PB2") (pinfunction "PB2/BOOT1_PB2") (pintype "bidirectional"))
      (node (ref "PROCESSOR_2") (pin "VSS") (pinfunction "VSS_1_VSS") (pintype "bidirectional"))
      (node (ref "PROCESSOR_2") (pin "VSS0") (pinfunction "VSS_2_VSS0") (pintype "bidirectional"))
      (node (ref "PROCESSOR_2") (pin "VSSA") (pinfunction "VSSA_VSSA") (pintype "bidirectional"))
      (node (ref "PWR_BRD1") (pin "1") (pinfunction "1_1") (pintype "passive"))
      (node (ref "Q1") (pin "2") (pinfunction "S_2") (pintype "passive"))
      (node (ref "R3") (pin "1") (pinfunction "1_1") (pintype "passive"))
      (node (ref "R5") (pin "2") (pinfunction "2_2") (pintype "passive"))
      (node (ref "RN4") (pin "3") (pinfunction "2_3") (pintype "passive"))
      (node (ref "RN5") (pin "3") (pinfunction "2_3") (pintype "passive"))
      (node (ref "RN6") (pin "3") (pinfunction "2_3") (pintype "passive"))
      (node (ref "U$2") (pin "6") (pinfunction "VSS_6") (pintype "power_in"))
      (node (ref "U$2") (pin "MT1") (pinfunction "GND_MT1") (pintype "power_in"))
      (node (ref "U$2") (pin "MT2") (pinfunction "GND1_MT2") (pintype "power_in"))
      (node (ref "U$3") (pin "P21") (pinfunction "P$2_P21") (pintype "bidirectional"))
      (node (ref "U$3") (pin "P22") (pinfunction "P$2_P22") (pintype "bidirectional"))
      (node (ref "U$3") (pin "P23") (pinfunction "P$2_P23") (pintype "bidirectional"))
      (node (ref "U$3") (pin "P24") (pinfunction "P$2_P24") (pintype "bidirectional"))
      (node (ref "U$4") (pin "GND") (pinfunction "GND_GND") (pintype "bidirectional"))
      (node (ref "U$7") (pin "P$2") (pinfunction "GND_P$2") (pintype "bidirectional"))
      (node (ref "USB_PROT") (pin "P$2") (pinfunction "P$2_P$2") (pintype "bidirectional"))
      (node (ref "X1") (pin "1") (pinfunction "S_1") (pintype "passive"))
      (node (ref "X3") (pin "5") (pinfunction "5_5") (pintype "passive"))
      (node (ref "X4") (pin "1") (pinfunction "S_1") (pintype "passive"))
    )
    (net (code "25") (name "IMU_SCL") (class "Default")
      (node (ref "PROCESSOR_2") (pin "PB10") (pinfunction "PB10/SPI2_SCK/I2S2_CK/S2C2_SCL/USART3_TX/TIM2_CH3_PB10") (pintype "bidirectional"))
      (node (ref "U$4") (pin "SCL") (pinfunction "SCL_SCL") (pintype "bidirectional"))
    )
    (net (code "26") (name "IMU_SDA") (class "Default")
      (node (ref "PROCESSOR_2") (pin "PB11") (pinfunction "PB11/I2C2_SDA/USART3_RX/TIM2_CH4_PB11") (pintype "bidirectional"))
      (node (ref "U$4") (pin "SDA") (pinfunction "SDA_SDA") (pintype "bidirectional"))
    )
    (net (code "27") (name "MISC_3") (class "Default")
      (node (ref "PROCESSOR_1") (pin "PA6") (pinfunction "PA6/SPI1_MISO/TIM8_BKIN/TIM13_CH1/TIM3_CH1/TIM1_BKIN_PA6") (pintype "bidirectional"))
      (node (ref "PROCESSOR_2") (pin "PA7") (pinfunction "PA7/SPI1_MOSI/TIM8_CH1N/TIM14_CH1/TIM3_CH2/TIM1_CH1N_PA7") (pintype "bidirectional"))
    )
    (net (code "28") (name "MISC_4") (class "Default")
      (node (ref "PROCESSOR_1") (pin "PA7") (pinfunction "PA7/SPI1_MOSI/TIM8_CH1N/TIM14_CH1/TIM3_CH2/TIM1_CH1N_PA7") (pintype "bidirectional"))
      (node (ref "PROCESSOR_2") (pin "PA6") (pinfunction "PA6/SPI1_MISO/TIM8_BKIN/TIM13_CH1/TIM3_CH1/TIM1_BKIN_PA6") (pintype "bidirectional"))
    )
    (net (code "29") (name "NRST") (class "Default")
      (node (ref "R17") (pin "2") (pinfunction "2_2") (pintype "passive"))
      (node (ref "R2") (pin "1") (pinfunction "1_1") (pintype "passive"))
      (node (ref "R7") (pin "1") (pinfunction "1_1") (pintype "passive"))
      (node (ref "TP3") (pin "TP") (pinfunction "TP_TP") (pintype "input"))
      (node (ref "U$3") (pin "P11") (pinfunction "P$1_P11") (pintype "bidirectional"))
      (node (ref "U$3") (pin "P12") (pinfunction "P$1_P12") (pintype "bidirectional"))
      (node (ref "X1") (pin "5") (pinfunction "S_5") (pintype "passive"))
      (node (ref "X4") (pin "5") (pinfunction "S_5") (pintype "passive"))
    )
    (net (code "30") (name "NRST_P1_SAV") (class "Default")
      (node (ref "PROCESSOR_1") (pin "NRST") (pinfunction "NRST_NRST") (pintype "bidirectional"))
      (node (ref "R7") (pin "2") (pinfunction "2_2") (pintype "passive"))
    )
    (net (code "31") (name "NRST_P2") (class "Default")
      (node (ref "PROCESSOR_1") (pin "PA5") (pinfunction "PA5/SPI1_SCK/TIM2_CH1_ETR/TIM8_CHIN_PA5") (pintype "bidirectional"))
      (node (ref "PROCESSOR_2") (pin "NRST") (pinfunction "NRST_NRST") (pintype "bidirectional"))
      (node (ref "R2") (pin "2") (pinfunction "2_2") (pintype "passive"))
    )
    (net (code "32") (name "Net-(C4-Pad1)") (class "Default")
      (node (ref "C4") (pin "1") (pinfunction "1_1") (pintype "passive"))
      (node (ref "PROCESSOR_1") (pin "VCAP_2") (pinfunction "VCAP_2_VCAP_2") (pintype "bidirectional"))
    )
    (net (code "33") (name "Net-(C9-Pad1)") (class "Default")
      (node (ref "C9") (pin "1") (pinfunction "1_1") (pintype "passive"))
      (node (ref "PROCESSOR_2") (pin "VCAP_1") (pinfunction "VCAP_1_VCAP_1") (pintype "bidirectional"))
    )
    (net (code "34") (name "Net-(C10-Pad1)") (class "Default")
      (node (ref "C10") (pin "1") (pinfunction "1_1") (pintype "passive"))
      (node (ref "PROCESSOR_1") (pin "VCAP_1") (pinfunction "VCAP_1_VCAP_1") (pintype "bidirectional"))
    )
    (net (code "35") (name "Net-(C13-Pad1)") (class "Default")
      (node (ref "C13") (pin "1") (pinfunction "1_1") (pintype "passive"))
      (node (ref "PROCESSOR_2") (pin "VCAP_2") (pinfunction "VCAP_2_VCAP_2") (pintype "bidirectional"))
    )
    (net (code "36") (name "Net-(D2-PadC)") (class "Default")
      (node (ref "D2") (pin "C") (pinfunction "C_C") (pintype "passive"))
      (node (ref "R18") (pin "1") (pinfunction "1_1") (pintype "passive"))
    )
    (net (code "37") (name "Net-(IC1-OUT)") (class "Default")
      (node (ref "IC1") (pin "4") (pinfunction "OUT_4") (pintype "output"))
      (node (ref "IC3") (pin "4") (pinfunction "OUT_4") (pintype "output"))
      (node (ref "IC4") (pin "4") (pinfunction "OUT_4") (pintype "output"))
      (node (ref "IC5") (pin "4") (pinfunction "OUT_4") (pintype "output"))
      (node (ref "IC6") (pin "4") (pinfunction "OUT_4") (pintype "output"))
      (node (ref "IC7") (pin "4") (pinfunction "OUT_4") (pintype "output"))
      (node (ref "R23") (pin "2") (pinfunction "2_2") (pintype "passive"))
      (node (ref "TP20") (pin "TP") (pinfunction "TP_TP") (pintype "input"))
      (node (ref "U$7") (pin "P$6") (pinfunction "NCLR_P$6") (pintype "bidirectional"))
    )
    (net (code "38") (name "Net-(P1_LED-PadA)") (class "Default")
      (node (ref "P1_LED") (pin "A") (pinfunction "A_A") (pintype "passive"))
      (node (ref "R9") (pin "1") (pinfunction "1_1") (pintype "passive"))
    )
    (net (code "39") (name "Net-(P2_LED-PadA)") (class "Default")
      (node (ref "P2_LED") (pin "A") (pinfunction "A_A") (pintype "passive"))
      (node (ref "R10") (pin "1") (pinfunction "1_1") (pintype "passive"))
    )
    (net (code "40") (name "Net-(PROCESSOR_1-PC3{slash}SPI2_MOSI{slash}I2S2_SD{slash})") (class "Default")
      (node (ref "P1_LED") (pin "C") (pinfunction "C_C") (pintype "passive"))
      (node (ref "PROCESSOR_1") (pin "PC3") (pinfunction "PC3/SPI2_MOSI/I2S2_SD/_PC3") (pintype "bidirectional"))
    )
    (net (code "41") (name "Net-(PROCESSOR_1-PH0{slash}OSC_IN)") (class "Default")
      (node (ref "C6") (pin "1") (pinfunction "1_1") (pintype "passive"))
      (node (ref "PROCESSOR_1") (pin "PH0") (pinfunction "PH0/OSC_IN_PH0") (pintype "bidirectional"))
      (node (ref "Y1") (pin "2") (pinfunction "2_2") (pintype "passive"))
    )
    (net (code "42") (name "Net-(PROCESSOR_1-PH1{slash}OSC_OUT)") (class "Default")
      (node (ref "C7") (pin "1") (pinfunction "1_1") (pintype "passive"))
      (node (ref "PROCESSOR_1") (pin "PH1") (pinfunction "PH1/OSC_OUT_PH1") (pintype "bidirectional"))
      (node (ref "Y1") (pin "1") (pinfunction "1_1") (pintype "passive"))
    )
    (net (code "43") (name "Net-(PROCESSOR_1-PadBOOT0)") (class "Default")
      (node (ref "PROCESSOR_1") (pin "BOOT0") (pinfunction "BOOT0_BOOT0") (pintype "bidirectional"))
      (node (ref "R4") (pin "1") (pinfunction "1_1") (pintype "passive"))
    )
    (net (code "44") (name "Net-(PROCESSOR_2-PC3{slash}SPI2_MOSI{slash}I2S2_SD{slash})") (class "Default")
      (node (ref "P2_LED") (pin "C") (pinfunction "C_C") (pintype "passive"))
      (node (ref "PROCESSOR_2") (pin "PC3") (pinfunction "PC3/SPI2_MOSI/I2S2_SD/_PC3") (pintype "bidirectional"))
    )
    (net (code "45") (name "Net-(Q1-D)") (class "Default")
      (node (ref "Q1") (pin "3") (pinfunction "D_3") (pintype "passive"))
      (node (ref "R13") (pin "1") (pinfunction "1_1") (pintype "passive"))
      (node (ref "U$6") (pin "P4") (pinfunction "G_P4") (pintype "passive"))
    )
    (net (code "46") (name "Net-(Q3-G)") (class "Default")
      (node (ref "Q3") (pin "1") (pinfunction "G_1") (pintype "bidirectional"))
      (node (ref "R26") (pin "2") (pinfunction "2_2") (pintype "passive"))
    )
    (net (code "47") (name "Net-(U$7-Q)") (class "Default")
      (node (ref "R15") (pin "1") (pinfunction "1_1") (pintype "passive"))
      (node (ref "U$7") (pin "P$4") (pinfunction "Q_P$4") (pintype "bidirectional"))
    )
    (net (code "48") (name "OBC_P1_2_P2") (class "Default")
      (node (ref "PROCESSOR_1") (pin "PA2") (pinfunction "PA2/USART2_TX/TIM5_CH3/TIM9_CH1/TIM2_CH3_PA2") (pintype "bidirectional"))
      (node (ref "PROCESSOR_2") (pin "PA10") (pinfunction "PA10/USART1_RX/TIM3_CH3_PA10") (pintype "bidirectional"))
      (node (ref "TP6") (pin "TP") (pinfunction "TP_TP") (pintype "input"))
    )
    (net (code "49") (name "OBC_P2_2_P1") (class "Default")
      (node (ref "PROCESSOR_1") (pin "PA3") (pinfunction "PA3/USART2_RX/TIM5_CH4/TIM9_CH2/TIM2_CH4_PA3") (pintype "bidirectional"))
      (node (ref "PROCESSOR_2") (pin "PA9") (pinfunction "PA9/USART1_TX/TIM1_CH2/I2C3_SMBA_PA9") (pintype "bidirectional"))
      (node (ref "TP5") (pin "TP") (pinfunction "TP_TP") (pintype "input"))
    )
    (net (code "50") (name "P1_SGN_PCKT") (class "Default")
      (node (ref "PROCESSOR_1") (pin "PA1") (pinfunction "PA1/USART2_RTS/UART4_RX/TIM5_CH2/TIM2_CH2_PA1") (pintype "bidirectional"))
      (node (ref "PROCESSOR_2") (pin "PA11") (pinfunction "PA11/USART1_CTS/CAN1_RX/TIM1_CH4_PA11") (pintype "bidirectional"))
      (node (ref "TP7") (pin "TP") (pinfunction "TP_TP") (pintype "input"))
    )
    (net (code "51") (name "P2_SGN_PCKT") (class "Default")
      (node (ref "PROCESSOR_1") (pin "PA0") (pinfunction "PA0/WKUP/USART2_CTS/UART4_TX/TIM2_CH1_ETR/TIM5_CH1/TIM8_ETR_PA0") (pintype "bidirectional"))
      (node (ref "PROCESSOR_2") (pin "PA12") (pinfunction "PA12/USART1_RTS/CAN1_TX/TIM1_ETR_PA12") (pintype "bidirectional"))
      (node (ref "TP8") (pin "TP") (pinfunction "TP_TP") (pintype "input"))
    )
    (net (code "52") (name "PWR_BRD_RX") (class "Default")
      (node (ref "PROCESSOR_2") (pin "PC7") (pinfunction "PC7/I2S3_MCK/TIM8_CH2/SDIO_D7/USART6_RX_PC7") (pintype "bidirectional"))
      (node (ref "PWR_BRD1") (pin "3") (pinfunction "3_3") (pintype "passive"))
    )
    (net (code "53") (name "PWR_BRD_TX") (class "Default")
      (node (ref "PROCESSOR_2") (pin "PC6") (pinfunction "PC6/I2S2_MCK/TIM8_CH1/SDIO_D6/USART6_TX/TIM3_CH1_PC6") (pintype "bidirectional"))
      (node (ref "PWR_BRD1") (pin "4") (pinfunction "4_4") (pintype "passive"))
    )
    (net (code "54") (name "SD_CLK") (class "Default")
      (node (ref "PROCESSOR_2") (pin "PC12") (pinfunction "PC12/UART5_TX/SDIO_CK/SPI3_MOSI/I2S3_SD/USART3_CK_PC12") (pintype "bidirectional"))
      (node (ref "RN1") (pin "6") (pinfunction "2_6") (pintype "passive"))
      (node (ref "U$2") (pin "5") (pinfunction "SCLK_5") (pintype "input"))
    )
    (net (code "55") (name "SD_CMD") (class "Default")
      (node (ref "PROCESSOR_2") (pin "PD2") (pinfunction "PD2/TIM3_ETR/UART5_RX/SDIO_CMD_PD2") (pintype "bidirectional"))
      (node (ref "U$2") (pin "3") (pinfunction "DATA_IN_3") (pintype "input"))
    )
    (net (code "56") (name "SD_D0") (class "Default")
      (node (ref "PROCESSOR_2") (pin "PC8") (pinfunction "PC8/TIM8_CH3/SDIO_D0/TIM3_CH3/USART6_CK_PC8") (pintype "bidirectional"))
      (node (ref "RN1") (pin "7") (pinfunction "2_7") (pintype "passive"))
      (node (ref "U$2") (pin "7") (pinfunction "DATA_OUT_7") (pintype "output"))
    )
    (net (code "57") (name "SD_D1") (class "Default")
      (node (ref "PROCESSOR_2") (pin "PC9") (pinfunction "PC9/I2S_CKIN/MCO2/TIM8_CH4/SDIO_D1/I2C3_SDA_PC9") (pintype "bidirectional"))
      (node (ref "RN1") (pin "8") (pinfunction "2_8") (pintype "passive"))
      (node (ref "U$2") (pin "8") (pinfunction "DAT1_8") (pintype "bidirectional"))
    )
    (net (code "58") (name "SD_D2") (class "Default")
      (node (ref "PROCESSOR_2") (pin "PC10") (pinfunction "PC10/SPI3_SCK/I2S3_CK/UART4_TX/SDIO_D2/USART3_TX_PC10") (pintype "bidirectional"))
      (node (ref "R16") (pin "1") (pinfunction "1_1") (pintype "passive"))
      (node (ref "U$2") (pin "1") (pinfunction "DAT2_1") (pintype "bidirectional"))
    )
    (net (code "59") (name "SD_D3") (class "Default")
      (node (ref "PROCESSOR_2") (pin "PC11") (pinfunction "PC11/UART4_RX/SPI3_MISO/SDIO_D3/USART3_RX/I2S3_EXT_SD_PC11") (pintype "bidirectional"))
      (node (ref "RN1") (pin "5") (pinfunction "2_5") (pintype "passive"))
      (node (ref "U$2") (pin "2") (pinfunction "CS_2") (pintype "input"))
    )
    (net (code "60") (name "SER_FROM_ODROID") (class "Default")
      (node (ref "PROCESSOR_1") (pin "PA10") (pinfunction "PA10/USART1_RX/TIM3_CH3_PA10") (pintype "bidirectional"))
      (node (ref "Q3") (pin "3") (pinfunction "D_3") (pintype "bidirectional"))
      (node (ref "R27") (pin "1") (pinfunction "1_1") (pintype "passive"))
      (node (ref "TP9") (pin "TP") (pinfunction "TP_TP") (pintype "input"))
    )
    (net (code "61") (name "SER_TO_ODROID") (class "Default")
      (node (ref "CON_ODROID1") (pin "2") (pinfunction "2_2") (pintype "passive"))
      (node (ref "PROCESSOR_1") (pin "PA9") (pinfunction "PA9/USART1_TX/TIM1_CH2/I2C3_SMBA_PA9") (pintype "bidirectional"))
      (node (ref "R32") (pin "1") (pinfunction "1_1") (pintype "passive"))
      (node (ref "TP10") (pin "TP") (pinfunction "TP_TP") (pintype "input"))
    )
    (net (code "62") (name "SLAVE_CLK") (class "Default")
      (node (ref "PROCESSOR_1") (pin "PA8") (pinfunction "PA8/MCO1/USART1_CK/TIM1_CH1/I2C3_SCL_PA8") (pintype "bidirectional"))
      (node (ref "PROCESSOR_2") (pin "PH0") (pinfunction "PH0/OSC_IN_PH0") (pintype "bidirectional"))
      (node (ref "TP4") (pin "TP") (pinfunction "TP_TP") (pintype "input"))
    )
    (net (code "63") (name "SND_SIG") (class "Default")
      (node (ref "R14") (pin "1") (pinfunction "1_1") (pintype "passive"))
      (node (ref "R6") (pin "1") (pinfunction "1_1") (pintype "passive"))
      (node (ref "TP11") (pin "TP") (pinfunction "TP_TP") (pintype "input"))
      (node (ref "U$1") (pin "P$2") (pinfunction "P$2_P$2") (pintype "bidirectional"))
    )
    (net (code "64") (name "SND_SIG_1") (class "Default")
      (node (ref "PROCESSOR_2") (pin "PA4") (pinfunction "PA4/SPI1_NSS/SPI3_NSS/USART2_CK/I2S3_WS_PA4") (pintype "bidirectional"))
      (node (ref "R6") (pin "2") (pinfunction "2_2") (pintype "passive"))
    )
    (net (code "65") (name "SND_SIG_2") (class "Default")
      (node (ref "PROCESSOR_2") (pin "PA5") (pinfunction "PA5/SPI1_SCK/TIM2_CH1_ETR/TIM8_CHIN_PA5") (pintype "bidirectional"))
      (node (ref "R14") (pin "2") (pinfunction "2_2") (pintype "passive"))
    )
    (net (code "66") (name "SWCLK_P1") (class "Default")
      (node (ref "PROCESSOR_1") (pin "PA14") (pinfunction "PA14/JTCK-SWCLK_PA14") (pintype "bidirectional"))
      (node (ref "X1") (pin "3") (pinfunction "S_3") (pintype "passive"))
    )
    (net (code "67") (name "SWCLK_P2") (class "Default")
      (node (ref "PROCESSOR_2") (pin "PA14") (pinfunction "PA14/JTCK-SWCLK_PA14") (pintype "bidirectional"))
      (node (ref "X4") (pin "3") (pinfunction "S_3") (pintype "passive"))
    )
    (net (code "68") (name "SWDIO_P1") (class "Default")
      (node (ref "PROCESSOR_1") (pin "PA13") (pinfunction "PA13/JTMS-SWDIO_PA13") (pintype "bidirectional"))
      (node (ref "X1") (pin "2") (pinfunction "S_2") (pintype "passive"))
    )
    (net (code "69") (name "SWDIO_P2") (class "Default")
      (node (ref "PROCESSOR_2") (pin "PA13") (pinfunction "PA13/JTMS-SWDIO_PA13") (pintype "bidirectional"))
      (node (ref "X4") (pin "2") (pinfunction "S_2") (pintype "passive"))
    )
    (net (code "70") (name "TRACESWO_P1") (class "Default")
      (node (ref "PROCESSOR_1") (pin "PB3") (pinfunction "PB3/JTDO/TRACESWO/SPI3_SCK/I2S3_CK/TIM2_CH2/SPI1_SCK_PB3") (pintype "bidirectional"))
      (node (ref "X1") (pin "4") (pinfunction "S_4") (pintype "passive"))
    )
    (net (code "71") (name "TRACESWO_P2") (class "Default")
      (node (ref "PROCESSOR_2") (pin "PB3") (pinfunction "PB3/JTDO/TRACESWO/SPI3_SCK/I2S3_CK/TIM2_CH2/SPI1_SCK_PB3") (pintype "bidirectional"))
      (node (ref "X4") (pin "4") (pinfunction "S_4") (pintype "passive"))
    )
    (net (code "72") (name "TX_ODROID") (class "Default")
      (node (ref "CON_ODROID1") (pin "3") (pinfunction "3_3") (pintype "passive"))
      (node (ref "Q3") (pin "2") (pinfunction "S_2") (pintype "bidirectional"))
    )
    (net (code "73") (name "USB_DM") (class "Default")
      (node (ref "PROCESSOR_1") (pin "PA11") (pinfunction "PA11/USART1_CTS/CAN1_RX/TIM1_CH4_PA11") (pintype "bidirectional"))
      (node (ref "TP2") (pin "TP") (pinfunction "TP_TP") (pintype "input"))
      (node (ref "USB_PROT") (pin "P$6") (pinfunction "P$6_P$6") (pintype "bidirectional"))
      (node (ref "X3") (pin "2") (pinfunction "2_2") (pintype "passive"))
    )
    (net (code "74") (name "USB_DP") (class "Default")
      (node (ref "PROCESSOR_1") (pin "PA12") (pinfunction "PA12/USART1_RTS/CAN1_TX/TIM1_ETR_PA12") (pintype "bidirectional"))
      (node (ref "TP1") (pin "TP") (pinfunction "TP_TP") (pintype "input"))
      (node (ref "USB_PROT") (pin "P$3") (pinfunction "P$3_P$3") (pintype "bidirectional"))
      (node (ref "X3") (pin "3") (pinfunction "3_3") (pintype "passive"))
    )
    (net (code "75") (name "USB_ID") (class "Default")
      (node (ref "USB_PROT") (pin "P$1") (pinfunction "P$1_P$1") (pintype "bidirectional"))
      (node (ref "X3") (pin "4") (pinfunction "4_4") (pintype "passive"))
    )
    (net (code "76") (name "USB_VBUS") (class "Default")
      (node (ref "USB_PROT") (pin "P$5") (pinfunction "P$5_P$5") (pintype "bidirectional"))
      (node (ref "X3") (pin "1") (pinfunction "1_1") (pintype "passive"))
    )
    (net (code "77") (name "USR_BTN1_A") (class "Default")
      (node (ref "PROCESSOR_1") (pin "PB5") (pinfunction "PB5/I2C1_SMBA/CAN2_RX/TIM3_CH2/SPI1_MOSI/SPI3_MOSI/I2S3_SD_PB5") (pintype "bidirectional"))
      (node (ref "R38") (pin "2") (pinfunction "2_2") (pintype "passive"))
      (node (ref "X2") (pin "9") (pinfunction "S_9") (pintype "passive"))
    )
    (net (code "78") (name "USR_BTN1_K") (class "Default")
      (node (ref "PROCESSOR_1") (pin "PB4") (pinfunction "PB4/NJTRST/SPI3_MISO/TIM3_CH1/SPI1_MISO/I2S3_EXT_SD_PB4") (pintype "bidirectional"))
      (node (ref "R33") (pin "1") (pinfunction "1_1") (pintype "passive"))
      (node (ref "X2") (pin "10") (pinfunction "S_10") (pintype "passive"))
    )
    (net (code "79") (name "USR_BTN2_A") (class "Default")
      (node (ref "PROCESSOR_1") (pin "PB7") (pinfunction "PB7/I2C1_SDA/USART1_RX/TIM4_CH2_PB7") (pintype "bidirectional"))
      (node (ref "R37") (pin "2") (pinfunction "2_2") (pintype "passive"))
      (node (ref "X2") (pin "7") (pinfunction "S_7") (pintype "passive"))
    )
    (net (code "80") (name "USR_BTN2_K") (class "Default")
      (node (ref "PROCESSOR_1") (pin "PB6") (pinfunction "PB6/I2C1_SCL/TIM4_CH1/CAN2_TX/USART1_TX_PB6") (pintype "bidirectional"))
      (node (ref "R12") (pin "1") (pinfunction "1_1") (pintype "passive"))
      (node (ref "X2") (pin "8") (pinfunction "S_8") (pintype "passive"))
    )
    (net (code "81") (name "USR_BTN3_A") (class "Default")
      (node (ref "PROCESSOR_1") (pin "PB14") (pinfunction "PB14/SPI2_MISO/TIM1_CH2N/TIM12_CH1/USART3_RTS/TIM8_CH2N/I2S2_EXT_SD_PB14") (pintype "bidirectional"))
      (node (ref "R36") (pin "2") (pinfunction "2_2") (pintype "passive"))
      (node (ref "X2") (pin "5") (pinfunction "S_5") (pintype "passive"))
    )
    (net (code "82") (name "USR_BTN3_K") (class "Default")
      (node (ref "PROCESSOR_1") (pin "PB9") (pinfunction "PB9/SPI2_NSS/I2S2_WS/TIM4_CH4/TIM11_CH1/SDIO_D5/I2C1_SDA/CAN1_TX_PB9") (pintype "bidirectional"))
      (node (ref "R11") (pin "1") (pinfunction "1_1") (pintype "passive"))
      (node (ref "X2") (pin "6") (pinfunction "S_6") (pintype "passive"))
    )
    (net (code "83") (name "USR_BTN4_A") (class "Default")
      (node (ref "PROCESSOR_1") (pin "PB12") (pinfunction "PB12/SPI2_NSS/I2S2/WS/I2C2_SMBA/USART3_CK/TIM1_BKIN/CAN2_RX_PB12") (pintype "bidirectional"))
      (node (ref "R35") (pin "2") (pinfunction "2_2") (pintype "passive"))
      (node (ref "X2") (pin "3") (pinfunction "S_3") (pintype "passive"))
    )
    (net (code "84") (name "USR_BTN4_K") (class "Default")
      (node (ref "PROCESSOR_1") (pin "PB13") (pinfunction "PB13/SPI2_SCK/I2S2_CK/USART3_CTS/TIM1_CH1N/CAN2_TX_PB13") (pintype "bidirectional"))
      (node (ref "R8") (pin "1") (pinfunction "1_1") (pintype "passive"))
      (node (ref "X2") (pin "4") (pinfunction "S_4") (pintype "passive"))
    )
    (net (code "85") (name "USR_BTN5_A") (class "Default")
      (node (ref "PROCESSOR_1") (pin "PB0") (pinfunction "PB0/TIM3_CH3/TIM8_CH2N//TIM1_CH2N_PB0") (pintype "bidirectional"))
      (node (ref "R34") (pin "2") (pinfunction "2_2") (pintype "passive"))
      (node (ref "X2") (pin "1") (pinfunction "S_1") (pintype "passive"))
    )
    (net (code "86") (name "USR_BTN5_K") (class "Default")
      (node (ref "PROCESSOR_1") (pin "PC15") (pinfunction "PC15/OSC32_OUT_PC15") (pintype "bidirectional"))
      (node (ref "R1") (pin "1") (pinfunction "1_1") (pintype "passive"))
      (node (ref "X2") (pin "2") (pinfunction "S_2") (pintype "passive"))
    )
    (net (code "87") (name "VCC") (class "Default")
      (node (ref "BLUBB") (pin "3") (pinfunction "U_OUT_3") (pintype "bidirectional"))
      (node (ref "C1") (pin "1") (pinfunction "1_1") (pintype "passive"))
      (node (ref "C16") (pin "+") (pinfunction "+_+") (pintype "passive"))
      (node (ref "C17") (pin "1") (pinfunction "1_1") (pintype "passive"))
      (node (ref "C2") (pin "1") (pinfunction "1_1") (pintype "passive"))
      (node (ref "C3") (pin "1") (pinfunction "1_1") (pintype "passive"))
      (node (ref "C5") (pin "1") (pinfunction "1_1") (pintype "passive"))
      (node (ref "IC12") (pin "8") (pinfunction "VCC_8") (pintype "power_in"))
      (node (ref "IC13") (pin "8") (pinfunction "VCC_8") (pintype "power_in"))
      (node (ref "IC2") (pin "8") (pinfunction "VCC_8") (pintype "power_in"))
      (node (ref "PROCESSOR_1") (pin "VBAT") (pinfunction "VBAT_VBAT") (pintype "bidirectional"))
      (node (ref "PROCESSOR_1") (pin "VDD") (pinfunction "VDD_1_VDD") (pintype "bidirectional"))
      (node (ref "PROCESSOR_1") (pin "VDD1") (pinfunction "VDD_2_VDD1") (pintype "bidirectional"))
      (node (ref "PROCESSOR_1") (pin "VDD2") (pinfunction "VDD_3_VDD2") (pintype "bidirectional"))
      (node (ref "PROCESSOR_1") (pin "VDD3") (pinfunction "VDD_4_VDD3") (pintype "bidirectional"))
      (node (ref "PROCESSOR_1") (pin "VDDA") (pinfunction "VDDA_VDDA") (pintype "bidirectional"))
      (node (ref "PROCESSOR_2") (pin "VBAT") (pinfunction "VBAT_VBAT") (pintype "bidirectional"))
      (node (ref "PROCESSOR_2") (pin "VDD") (pinfunction "VDD_1_VDD") (pintype "bidirectional"))
      (node (ref "PROCESSOR_2") (pin "VDD1") (pinfunction "VDD_2_VDD1") (pintype "bidirectional"))
      (node (ref "PROCESSOR_2") (pin "VDD2") (pinfunction "VDD_3_VDD2") (pintype "bidirectional"))
      (node (ref "PROCESSOR_2") (pin "VDD3") (pinfunction "VDD_4_VDD3") (pintype "bidirectional"))
      (node (ref "PROCESSOR_2") (pin "VDDA") (pinfunction "VDDA_VDDA") (pintype "bidirectional"))
      (node (ref "R1") (pin "2") (pinfunction "2_2") (pintype "passive"))
      (node (ref "R10") (pin "2") (pinfunction "2_2") (pintype "passive"))
      (node (ref "R11") (pin "2") (pinfunction "2_2") (pintype "passive"))
      (node (ref "R12") (pin "2") (pinfunction "2_2") (pintype "passive"))
      (node (ref "R16") (pin "2") (pinfunction "2_2") (pintype "passive"))
      (node (ref "R17") (pin "1") (pinfunction "1_1") (pintype "passive"))
      (node (ref "R23") (pin "1") (pinfunction "1_1") (pintype "passive"))
      (node (ref "R27") (pin "2") (pinfunction "2_2") (pintype "passive"))
      (node (ref "R33") (pin "2") (pinfunction "2_2") (pintype "passive"))
      (node (ref "R34") (pin "1") (pinfunction "1_1") (pintype "passive"))
      (node (ref "R35") (pin "1") (pinfunction "1_1") (pintype "passive"))
      (node (ref "R36") (pin "1") (pinfunction "1_1") (pintype "passive"))
      (node (ref "R37") (pin "1") (pinfunction "1_1") (pintype "passive"))
      (node (ref "R38") (pin "1") (pinfunction "1_1") (pintype "passive"))
      (node (ref "R8") (pin "2") (pinfunction "2_2") (pintype "passive"))
      (node (ref "R9") (pin "2") (pinfunction "2_2") (pintype "passive"))
      (node (ref "RN1") (pin "1") (pinfunction "1_1") (pintype "passive"))
      (node (ref "RN1") (pin "2") (pinfunction "1_2") (pintype "passive"))
      (node (ref "RN1") (pin "3") (pinfunction "1_3") (pintype "passive"))
      (node (ref "RN1") (pin "4") (pinfunction "1_4") (pintype "passive"))
      (node (ref "RN4") (pin "4") (pinfunction "2_4") (pintype "passive"))
      (node (ref "RN5") (pin "4") (pinfunction "2_4") (pintype "passive"))
      (node (ref "RN6") (pin "4") (pinfunction "2_4") (pintype "passive"))
      (node (ref "U$2") (pin "4") (pinfunction "VDD_4") (pintype "power_in"))
      (node (ref "U$4") (pin "VDD") (pinfunction "VDD_VDD") (pintype "bidirectional"))
      (node (ref "U$4") (pin "VIN") (pinfunction "VIN_VIN") (pintype "bidirectional"))
      (node (ref "U$7") (pin "P$5") (pinfunction "VCC_P$5") (pintype "bidirectional"))
      (node (ref "X1") (pin "6") (pinfunction "S_6") (pintype "passive"))
      (node (ref "X4") (pin "6") (pinfunction "S_6") (pintype "passive"))
    )
    (net (code "88") (name "VCC_5V") (class "Default")
      (node (ref "BLUBB") (pin "1") (pinfunction "U_IN_1") (pintype "bidirectional"))
      (node (ref "C15") (pin "1") (pinfunction "1_1") (pintype "passive"))
      (node (ref "PWR_BRD1") (pin "2") (pinfunction "2_2") (pintype "passive"))
      (node (ref "U$1") (pin "P$1") (pinfunction "P$1_P$1") (pintype "bidirectional"))
    )
    (net (code "89") (name "VCC_BAT") (class "Default")
      (node (ref "DYNAMIXEL_LEFT_LEG") (pin "3") (pinfunction "3_3") (pintype "passive"))
      (node (ref "DYNAMIXEL_RIGHT_LEG") (pin "3") (pinfunction "3_3") (pintype "passive"))
      (node (ref "DYNAMIXEL_TORSO") (pin "3") (pinfunction "3_3") (pintype "passive"))
      (node (ref "TP22") (pin "TP") (pinfunction "TP_TP") (pintype "input"))
      (node (ref "U$6") (pin "P5") (pinfunction "D_P5") (pintype "passive"))
      (node (ref "U$6") (pin "P6") (pinfunction "D_P6") (pintype "passive"))
      (node (ref "U$6") (pin "P7") (pinfunction "D_P7") (pintype "passive"))
      (node (ref "U$6") (pin "P8") (pinfunction "D_P8") (pintype "passive"))
    )
    (net (code "90") (name "VCC_BAT_PRE") (class "Default")
      (node (ref "D2") (pin "A") (pinfunction "A_A") (pintype "passive"))
      (node (ref "DYNAMIXEL_PWR") (pin "3") (pinfunction "3_3") (pintype "passive"))
      (node (ref "IC1") (pin "5") (pinfunction "V+_5") (pintype "power_in"))
      (node (ref "IC3") (pin "5") (pinfunction "V+_5") (pintype "power_in"))
      (node (ref "IC4") (pin "5") (pinfunction "V+_5") (pintype "power_in"))
      (node (ref "IC5") (pin "5") (pinfunction "V+_5") (pintype "power_in"))
      (node (ref "IC6") (pin "5") (pinfunction "V+_5") (pintype "power_in"))
      (node (ref "IC7") (pin "5") (pinfunction "V+_5") (pintype "power_in"))
      (node (ref "R13") (pin "2") (pinfunction "2_2") (pintype "passive"))
      (node (ref "U$6") (pin "P1") (pinfunction "S_P1") (pintype "passive"))
      (node (ref "U$6") (pin "P2") (pinfunction "S_P2") (pintype "passive"))
      (node (ref "U$6") (pin "P3") (pinfunction "S_P3") (pintype "passive"))
    )
    (net (code "91") (name "VCC_ODROID") (class "Default")
      (node (ref "CON_ODROID1") (pin "4") (pinfunction "4_4") (pintype "passive"))
      (node (ref "R26") (pin "1") (pinfunction "1_1") (pintype "passive"))
      (node (ref "R32") (pin "2") (pinfunction "2_2") (pintype "passive"))
    )
    (net (code "92") (name "V_SAFETY_REF") (class "Default")
      (node (ref "C11") (pin "1") (pinfunction "1_1") (pintype "passive"))
      (node (ref "D1") (pin "C") (pinfunction "C_C") (pintype "passive"))
      (node (ref "IC1") (pin "3") (pinfunction "+IN_3") (pintype "input"))
      (node (ref "IC3") (pin "3") (pinfunction "+IN_3") (pintype "input"))
      (node (ref "IC4") (pin "3") (pinfunction "+IN_3") (pintype "input"))
      (node (ref "IC5") (pin "3") (pinfunction "+IN_3") (pintype "input"))
      (node (ref "IC6") (pin "3") (pinfunction "+IN_3") (pintype "input"))
      (node (ref "IC7") (pin "3") (pinfunction "+IN_3") (pintype "input"))
      (node (ref "R18") (pin "2") (pinfunction "2_2") (pintype "passive"))
      (node (ref "TP21") (pin "TP") (pinfunction "TP_TP") (pintype "input"))
    )
    (net (code "93") (name "unconnected-(PROCESSOR_1-PA15{slash}JTDI{slash}SPI3_NSS{slash}I2S3_WS{slash}TIM2_CH1_ETR{slash}SPI1_NSS-PadPA15)") (class "Default")
      (node (ref "PROCESSOR_1") (pin "PA15") (pinfunction "PA15/JTDI/SPI3_NSS/I2S3_WS/TIM2_CH1_ETR/SPI1_NSS_PA15") (pintype "bidirectional"))
    )
    (net (code "94") (name "unconnected-(PROCESSOR_1-PC2{slash}SPI2_MISO{slash}I2S2_EXT_SD-PadPC2)") (class "Default")
      (node (ref "PROCESSOR_1") (pin "PC2") (pinfunction "PC2/SPI2_MISO/I2S2_EXT_SD_PC2") (pintype "bidirectional"))
    )
    (net (code "95") (name "unconnected-(PROCESSOR_1-PC6{slash}I2S2_MCK{slash}TIM8_CH1{slash}SDIO_D6{slash}USART6_TX{slash}TIM3_CH1-PadPC6)") (class "Default")
      (node (ref "PROCESSOR_1") (pin "PC6") (pinfunction "PC6/I2S2_MCK/TIM8_CH1/SDIO_D6/USART6_TX/TIM3_CH1_PC6") (pintype "bidirectional"))
    )
    (net (code "96") (name "unconnected-(PROCESSOR_1-PC9{slash}I2S_CKIN{slash}MCO2{slash}TIM8_CH4{slash}SDIO_D1{slash}I2C3_SDA-PadPC9)") (class "Default")
      (node (ref "PROCESSOR_1") (pin "PC9") (pinfunction "PC9/I2S_CKIN/MCO2/TIM8_CH4/SDIO_D1/I2C3_SDA_PC9") (pintype "bidirectional"))
    )
    (net (code "97") (name "unconnected-(PROCESSOR_1-PadPC4)") (class "Default")
      (node (ref "PROCESSOR_1") (pin "PC4") (pinfunction "PC4_PC4") (pintype "bidirectional"))
    )
    (net (code "98") (name "unconnected-(PROCESSOR_2-PA0{slash}WKUP{slash}USART2_CTS{slash}UART4_TX{slash}TIM2_CH1_ETR{slash}TIM5_CH1{slash}TIM8_ETR-PadPA0)") (class "Default")
      (node (ref "PROCESSOR_2") (pin "PA0") (pinfunction "PA0/WKUP/USART2_CTS/UART4_TX/TIM2_CH1_ETR/TIM5_CH1/TIM8_ETR_PA0") (pintype "bidirectional"))
    )
    (net (code "99") (name "unconnected-(PROCESSOR_2-PA1{slash}USART2_RTS{slash}UART4_RX{slash}TIM5_CH2{slash}TIM2_CH2-PadPA1)") (class "Default")
      (node (ref "PROCESSOR_2") (pin "PA1") (pinfunction "PA1/USART2_RTS/UART4_RX/TIM5_CH2/TIM2_CH2_PA1") (pintype "bidirectional"))
    )
    (net (code "100") (name "unconnected-(PROCESSOR_2-PA2{slash}USART2_TX{slash}TIM5_CH3{slash}TIM9_CH1{slash}TIM2_CH3-PadPA2)") (class "Default")
      (node (ref "PROCESSOR_2") (pin "PA2") (pinfunction "PA2/USART2_TX/TIM5_CH3/TIM9_CH1/TIM2_CH3_PA2") (pintype "bidirectional"))
    )
    (net (code "101") (name "unconnected-(PROCESSOR_2-PA3{slash}USART2_RX{slash}TIM5_CH4{slash}TIM9_CH2{slash}TIM2_CH4-PadPA3)") (class "Default")
      (node (ref "PROCESSOR_2") (pin "PA3") (pinfunction "PA3/USART2_RX/TIM5_CH4/TIM9_CH2/TIM2_CH4_PA3") (pintype "bidirectional"))
    )
    (net (code "102") (name "unconnected-(PROCESSOR_2-PA8{slash}MCO1{slash}USART1_CK{slash}TIM1_CH1{slash}I2C3_SCL-PadPA8)") (class "Default")
      (node (ref "PROCESSOR_2") (pin "PA8") (pinfunction "PA8/MCO1/USART1_CK/TIM1_CH1/I2C3_SCL_PA8") (pintype "bidirectional"))
    )
    (net (code "103") (name "unconnected-(PROCESSOR_2-PA15{slash}JTDI{slash}SPI3_NSS{slash}I2S3_WS{slash}TIM2_CH1_ETR{slash}SPI1_NSS-PadPA15)") (class "Default")
      (node (ref "PROCESSOR_2") (pin "PA15") (pinfunction "PA15/JTDI/SPI3_NSS/I2S3_WS/TIM2_CH1_ETR/SPI1_NSS_PA15") (pintype "bidirectional"))
    )
    (net (code "104") (name "unconnected-(PROCESSOR_2-PB0{slash}TIM3_CH3{slash}TIM8_CH2N{slash}{slash}TIM1_CH2N-PadPB0)") (class "Default")
      (node (ref "PROCESSOR_2") (pin "PB0") (pinfunction "PB0/TIM3_CH3/TIM8_CH2N//TIM1_CH2N_PB0") (pintype "bidirectional"))
    )
    (net (code "105") (name "unconnected-(PROCESSOR_2-PB1{slash}TIM3_CH4{slash}TIM8_CH3N{slash}TIM1_CH3N-PadPB1)") (class "Default")
      (node (ref "PROCESSOR_2") (pin "PB1") (pinfunction "PB1/TIM3_CH4/TIM8_CH3N/TIM1_CH3N_PB1") (pintype "bidirectional"))
    )
    (net (code "106") (name "unconnected-(PROCESSOR_2-PB4{slash}NJTRST{slash}SPI3_MISO{slash}TIM3_CH1{slash}SPI1_MISO{slash}I2S3_EXT_SD-PadPB4)") (class "Default")
      (node (ref "PROCESSOR_2") (pin "PB4") (pinfunction "PB4/NJTRST/SPI3_MISO/TIM3_CH1/SPI1_MISO/I2S3_EXT_SD_PB4") (pintype "bidirectional"))
    )
    (net (code "107") (name "unconnected-(PROCESSOR_2-PB5{slash}I2C1_SMBA{slash}CAN2_RX{slash}TIM3_CH2{slash}SPI1_MOSI{slash}SPI3_MOSI{slash}I2S3_SD-PadPB5)") (class "Default")
      (node (ref "PROCESSOR_2") (pin "PB5") (pinfunction "PB5/I2C1_SMBA/CAN2_RX/TIM3_CH2/SPI1_MOSI/SPI3_MOSI/I2S3_SD_PB5") (pintype "bidirectional"))
    )
    (net (code "108") (name "unconnected-(PROCESSOR_2-PB6{slash}I2C1_SCL{slash}TIM4_CH1{slash}CAN2_TX{slash}USART1_TX-PadPB6)") (class "Default")
      (node (ref "PROCESSOR_2") (pin "PB6") (pinfunction "PB6/I2C1_SCL/TIM4_CH1/CAN2_TX/USART1_TX_PB6") (pintype "bidirectional"))
    )
    (net (code "109") (name "unconnected-(PROCESSOR_2-PB7{slash}I2C1_SDA{slash}USART1_RX{slash}TIM4_CH2-PadPB7)") (class "Default")
      (node (ref "PROCESSOR_2") (pin "PB7") (pinfunction "PB7/I2C1_SDA/USART1_RX/TIM4_CH2_PB7") (pintype "bidirectional"))
    )
    (net (code "110") (name "unconnected-(PROCESSOR_2-PB8{slash}TIM4_CH3{slash}SDIO_D4{slash}TIM10_CH1{slash}I2C1_SCL{slash}CAN1_RX-PadPB8)") (class "Default")
      (node (ref "PROCESSOR_2") (pin "PB8") (pinfunction "PB8/TIM4_CH3/SDIO_D4/TIM10_CH1/I2C1_SCL/CAN1_RX_PB8") (pintype "bidirectional"))
    )
    (net (code "111") (name "unconnected-(PROCESSOR_2-PB9{slash}SPI2_NSS{slash}I2S2_WS{slash}TIM4_CH4{slash}TIM11_CH1{slash}SDIO_D5{slash}I2C1_SDA{slash}CAN1_TX-PadPB9)") (class "Default")
      (node (ref "PROCESSOR_2") (pin "PB9") (pinfunction "PB9/SPI2_NSS/I2S2_WS/TIM4_CH4/TIM11_CH1/SDIO_D5/I2C1_SDA/CAN1_TX_PB9") (pintype "bidirectional"))
    )
    (net (code "112") (name "unconnected-(PROCESSOR_2-PB12{slash}SPI2_NSS{slash}I2S2{slash}WS{slash}I2C2_SMBA{slash}USART3_CK{slash}TIM1_BKIN{slash}CAN2_RX-PadPB12)") (class "Default")
      (node (ref "PROCESSOR_2") (pin "PB12") (pinfunction "PB12/SPI2_NSS/I2S2/WS/I2C2_SMBA/USART3_CK/TIM1_BKIN/CAN2_RX_PB12") (pintype "bidirectional"))
    )
    (net (code "113") (name "unconnected-(PROCESSOR_2-PB13{slash}SPI2_SCK{slash}I2S2_CK{slash}USART3_CTS{slash}TIM1_CH1N{slash}CAN2_TX-PadPB13)") (class "Default")
      (node (ref "PROCESSOR_2") (pin "PB13") (pinfunction "PB13/SPI2_SCK/I2S2_CK/USART3_CTS/TIM1_CH1N/CAN2_TX_PB13") (pintype "bidirectional"))
    )
    (net (code "114") (name "unconnected-(PROCESSOR_2-PB14{slash}SPI2_MISO{slash}TIM1_CH2N{slash}TIM12_CH1{slash}USART3_RTS{slash}TIM8_CH2N{slash}I2S2_EXT_SD-PadPB14)") (class "Default")
      (node (ref "PROCESSOR_2") (pin "PB14") (pinfunction "PB14/SPI2_MISO/TIM1_CH2N/TIM12_CH1/USART3_RTS/TIM8_CH2N/I2S2_EXT_SD_PB14") (pintype "bidirectional"))
    )
    (net (code "115") (name "unconnected-(PROCESSOR_2-PB15{slash}SPI2_MOSI{slash}I2S2_SD{slash}TIM1_CH3N{slash}TIM8_CH3N{slash}TIM12_CH2-PadPB15)") (class "Default")
      (node (ref "PROCESSOR_2") (pin "PB15") (pinfunction "PB15/SPI2_MOSI/I2S2_SD/TIM1_CH3N/TIM8_CH3N/TIM12_CH2_PB15") (pintype "bidirectional"))
    )
    (net (code "116") (name "unconnected-(PROCESSOR_2-PC2{slash}SPI2_MISO{slash}I2S2_EXT_SD-PadPC2)") (class "Default")
      (node (ref "PROCESSOR_2") (pin "PC2") (pinfunction "PC2/SPI2_MISO/I2S2_EXT_SD_PC2") (pintype "bidirectional"))
    )
    (net (code "117") (name "unconnected-(PROCESSOR_2-PC14{slash}OSC32_IN-PadPC14)") (class "Default")
      (node (ref "PROCESSOR_2") (pin "PC14") (pinfunction "PC14/OSC32_IN_PC14") (pintype "bidirectional"))
    )
    (net (code "118") (name "unconnected-(PROCESSOR_2-PC15{slash}OSC32_OUT-PadPC15)") (class "Default")
      (node (ref "PROCESSOR_2") (pin "PC15") (pinfunction "PC15/OSC32_OUT_PC15") (pintype "bidirectional"))
    )
    (net (code "119") (name "unconnected-(PROCESSOR_2-PH1{slash}OSC_OUT-PadPH1)") (class "Default")
      (node (ref "PROCESSOR_2") (pin "PH1") (pinfunction "PH1/OSC_OUT_PH1") (pintype "bidirectional"))
    )
    (net (code "120") (name "unconnected-(PROCESSOR_2-PadPC0)") (class "Default")
      (node (ref "PROCESSOR_2") (pin "PC0") (pinfunction "PC0_PC0") (pintype "bidirectional"))
    )
    (net (code "121") (name "unconnected-(PROCESSOR_2-PadPC1)") (class "Default")
      (node (ref "PROCESSOR_2") (pin "PC1") (pinfunction "PC1_PC1") (pintype "bidirectional"))
    )
    (net (code "122") (name "unconnected-(PROCESSOR_2-PadPC4)") (class "Default")
      (node (ref "PROCESSOR_2") (pin "PC4") (pinfunction "PC4_PC4") (pintype "bidirectional"))
    )
    (net (code "123") (name "unconnected-(PROCESSOR_2-PadPC5)") (class "Default")
      (node (ref "PROCESSOR_2") (pin "PC5") (pinfunction "PC5_PC5") (pintype "bidirectional"))
    )
    (net (code "124") (name "unconnected-(PROCESSOR_2-PadPC13)") (class "Default")
      (node (ref "PROCESSOR_2") (pin "PC13") (pinfunction "PC13_PC13") (pintype "bidirectional"))
    )
    (net (code "125") (name "unconnected-(U$2-CARD_DETECT-PadCD1)") (class "Default")
      (node (ref "U$2") (pin "CD1") (pinfunction "CARD_DETECT_CD1") (pintype "passive"))
    )
    (net (code "126") (name "unconnected-(U$2-CARD_DETECT1-PadCD2)") (class "Default")
      (node (ref "U$2") (pin "CD2") (pinfunction "CARD_DETECT1_CD2") (pintype "passive"))
    )
    (net (code "127") (name "unconnected-(USB_PROT-PadP$4)") (class "Default")
      (node (ref "USB_PROT") (pin "P$4") (pinfunction "P$4_P$4") (pintype "bidirectional"))
    )
  )
)
